# ComputeCalculator_V1_0.net
KiCad netlist of a schematic drawn in EAGLE
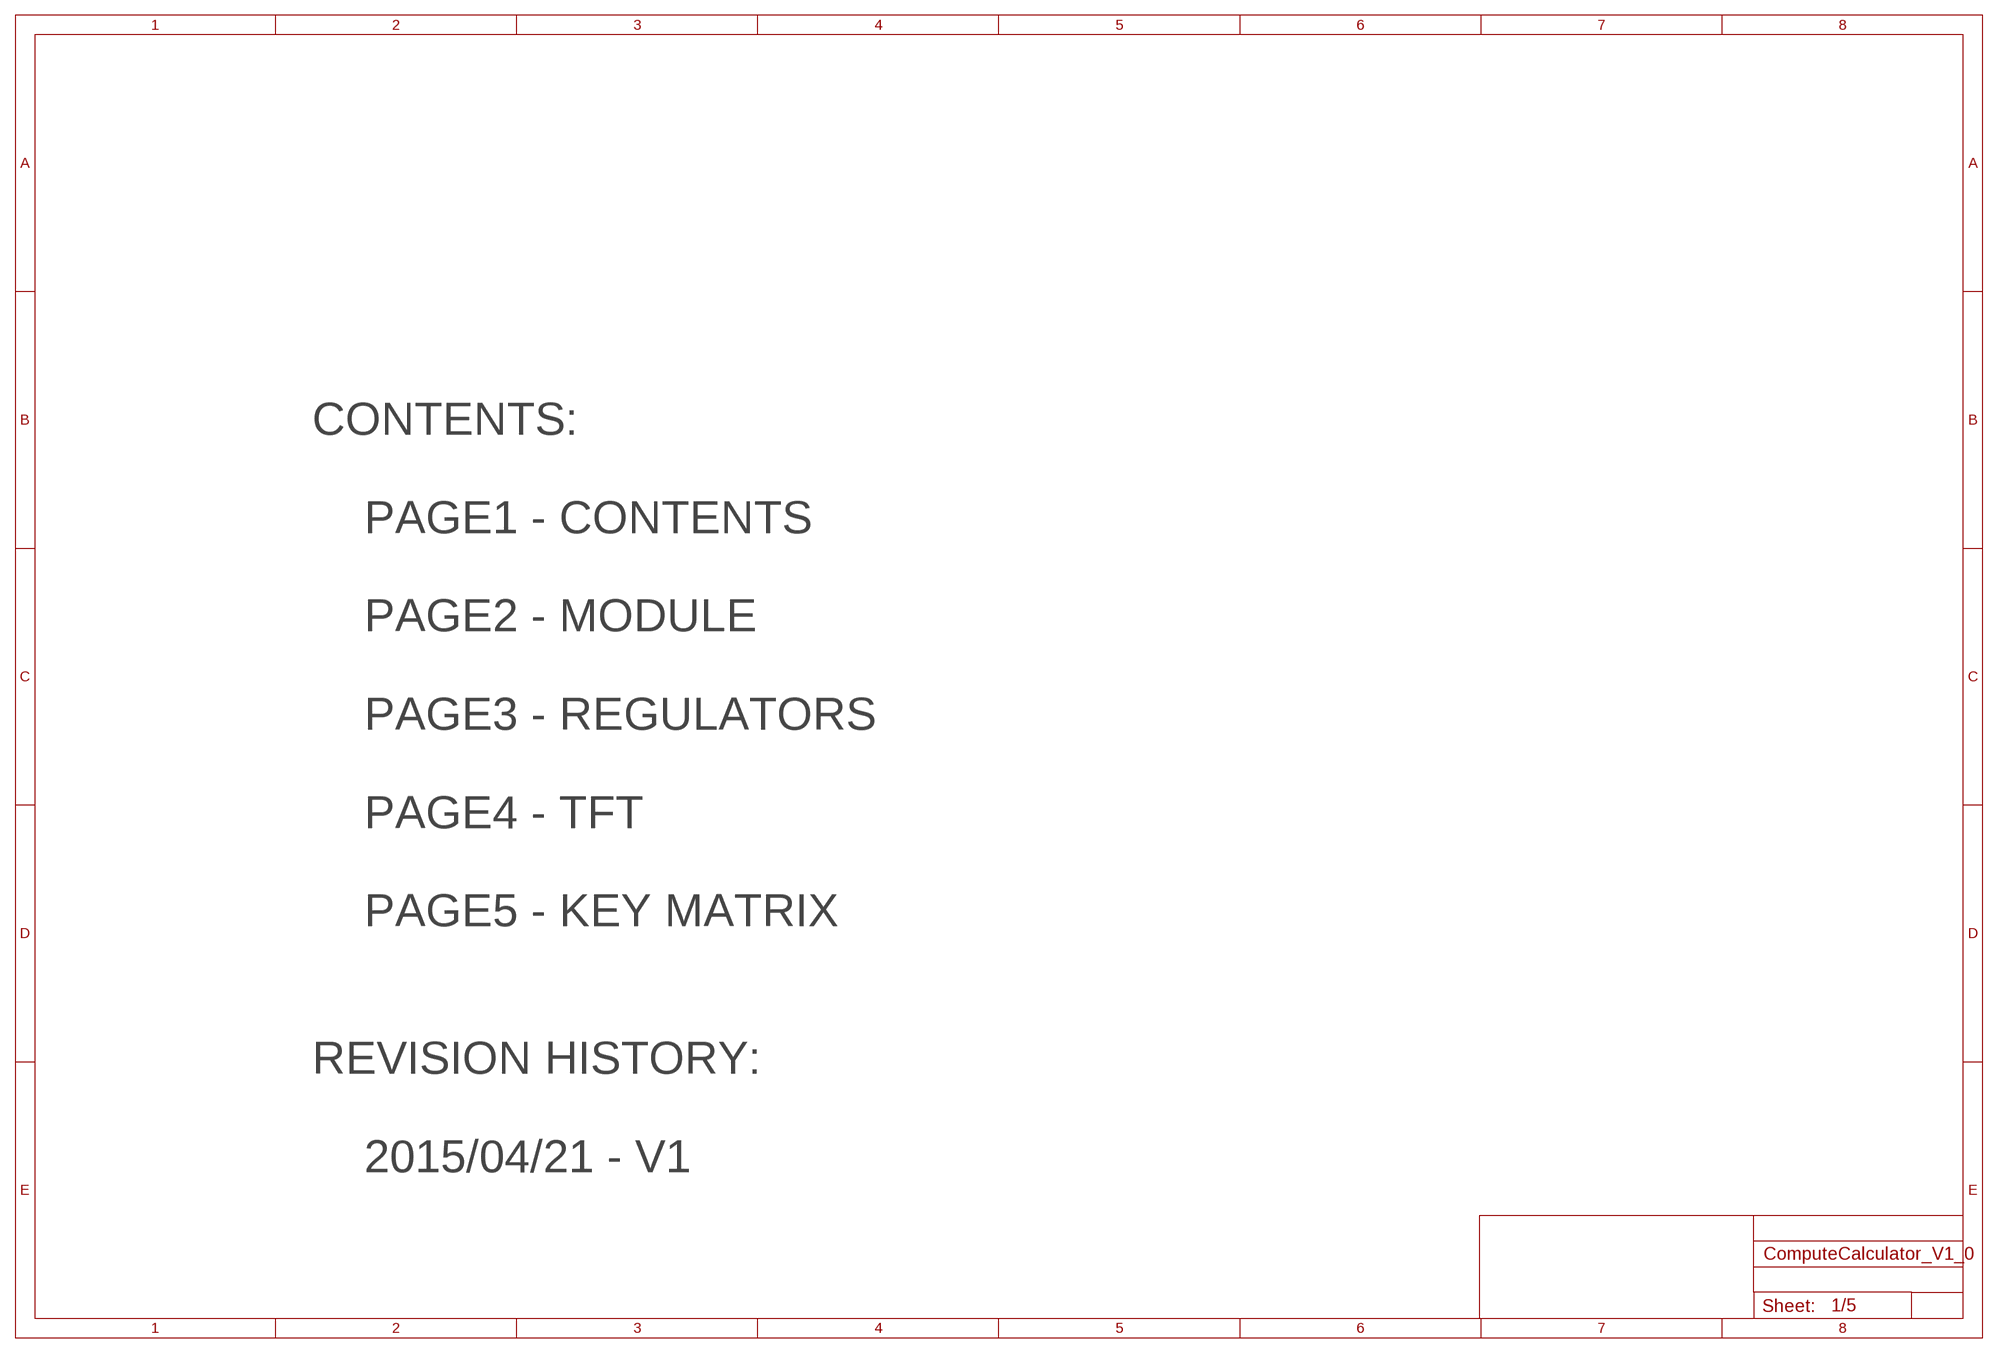
[diagram p0: schematic, sheet 1]
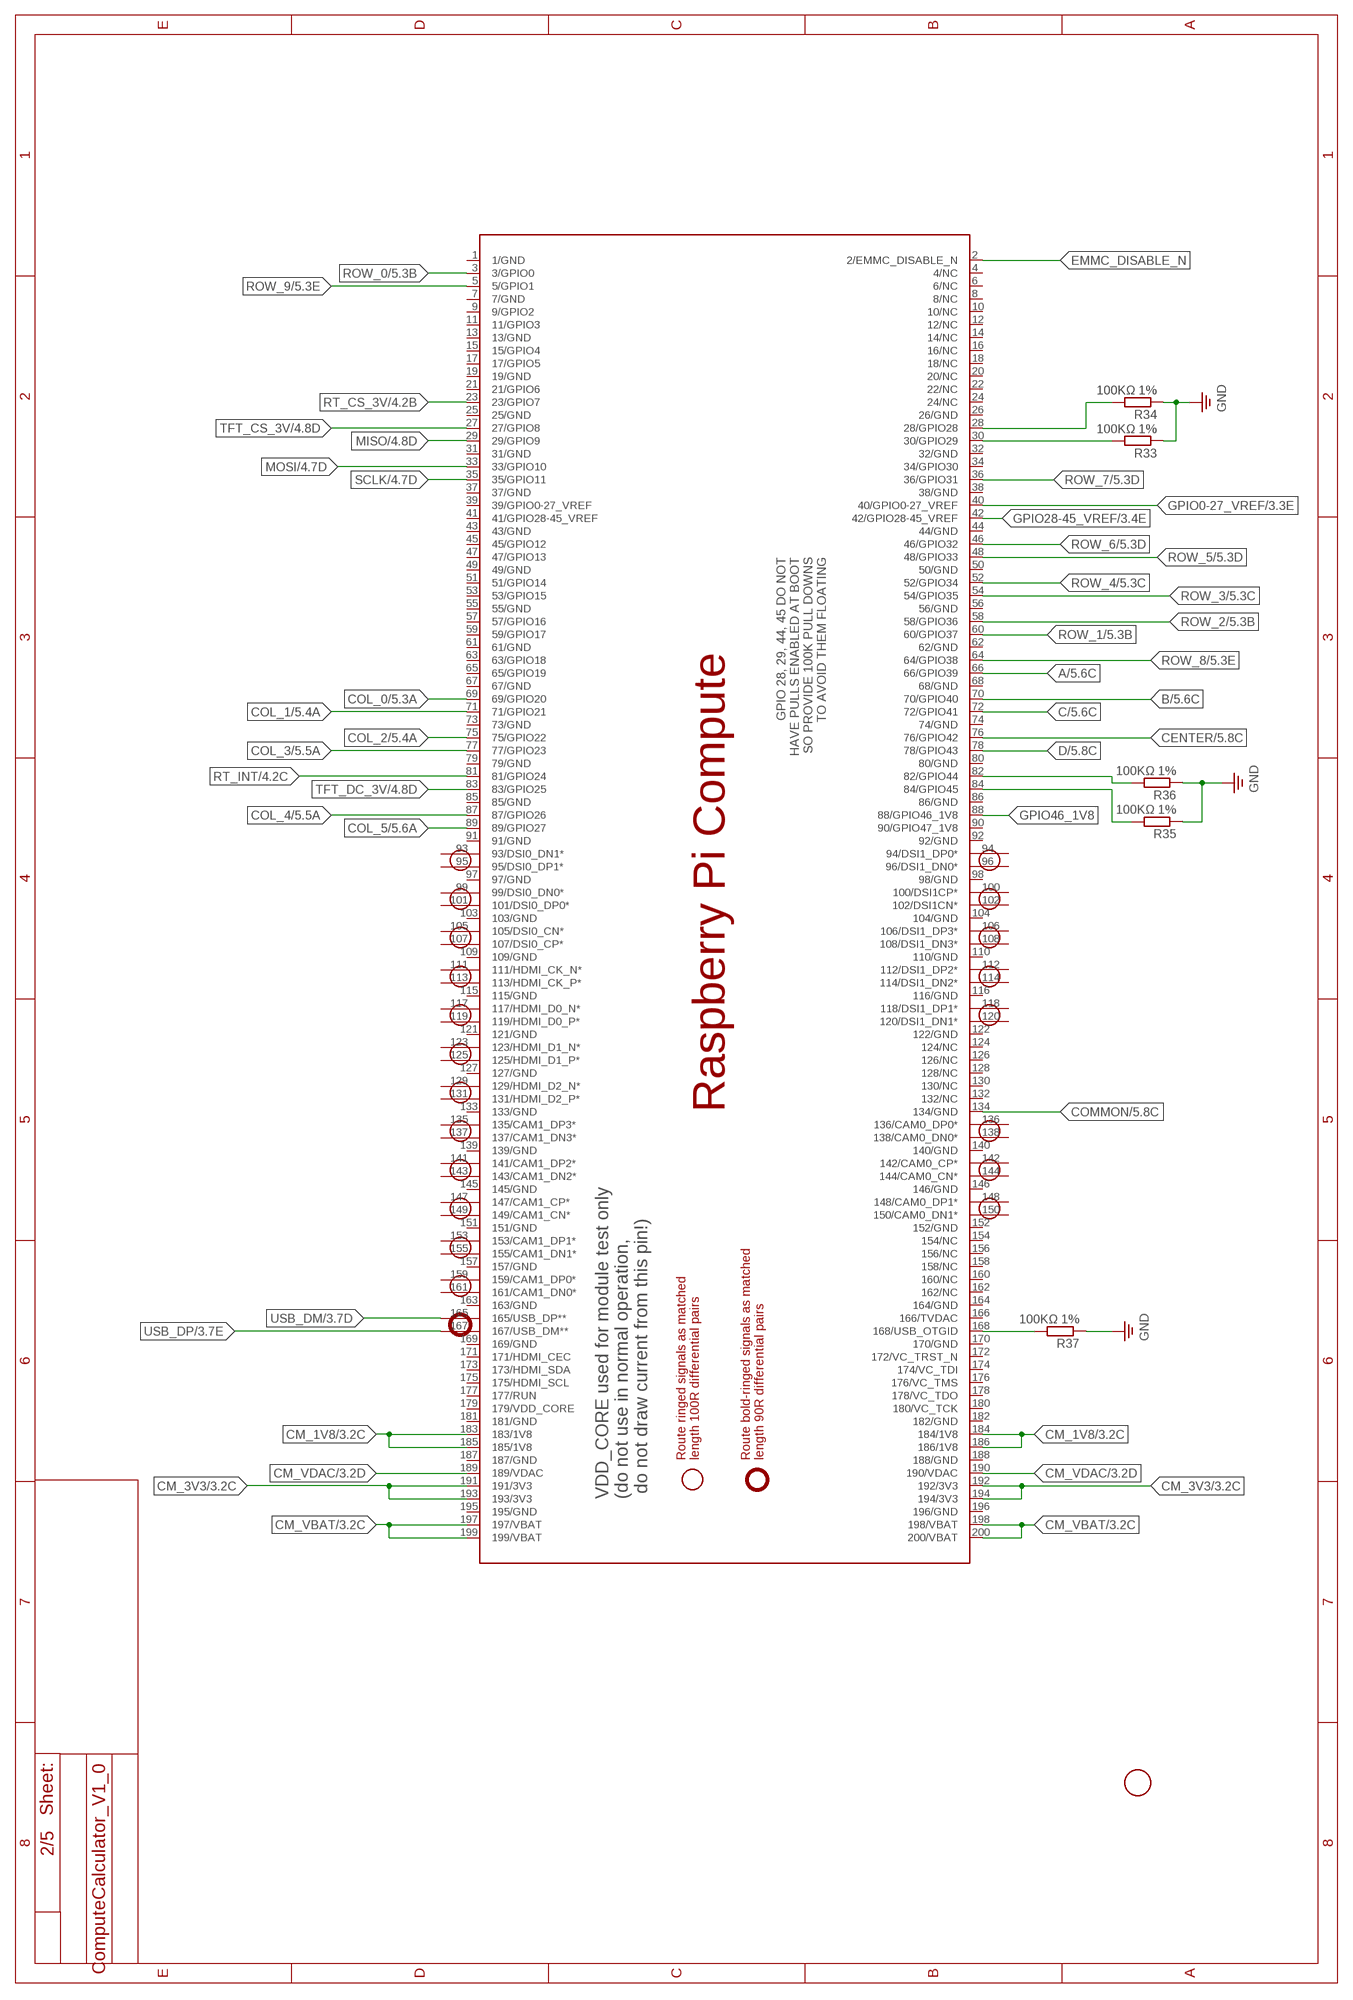
[diagram p1: schematic, sheet 2]
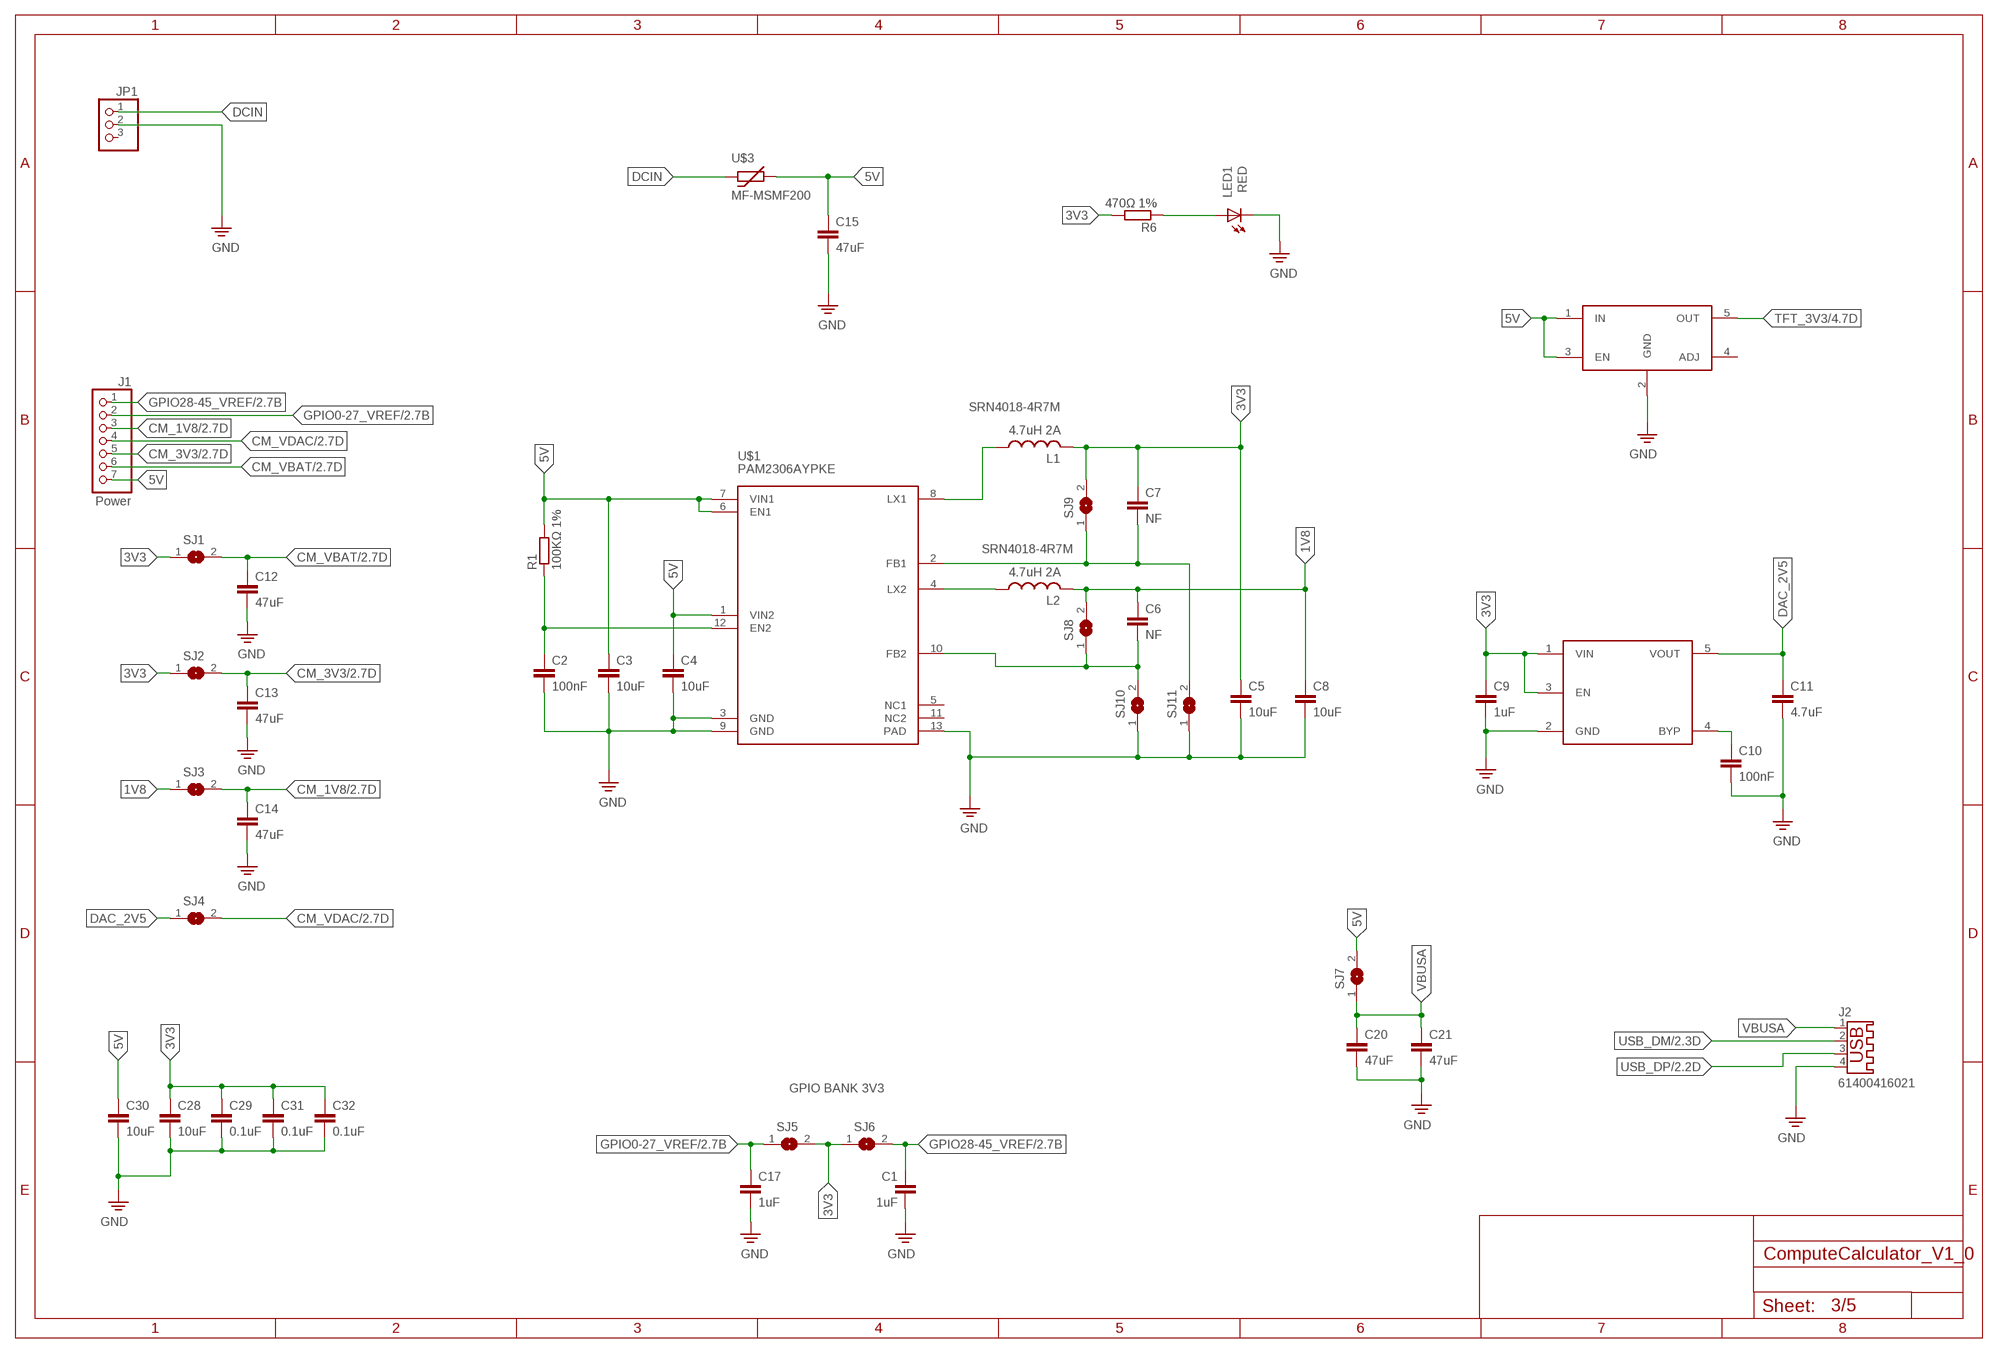
[diagram p2: schematic, sheet 3]
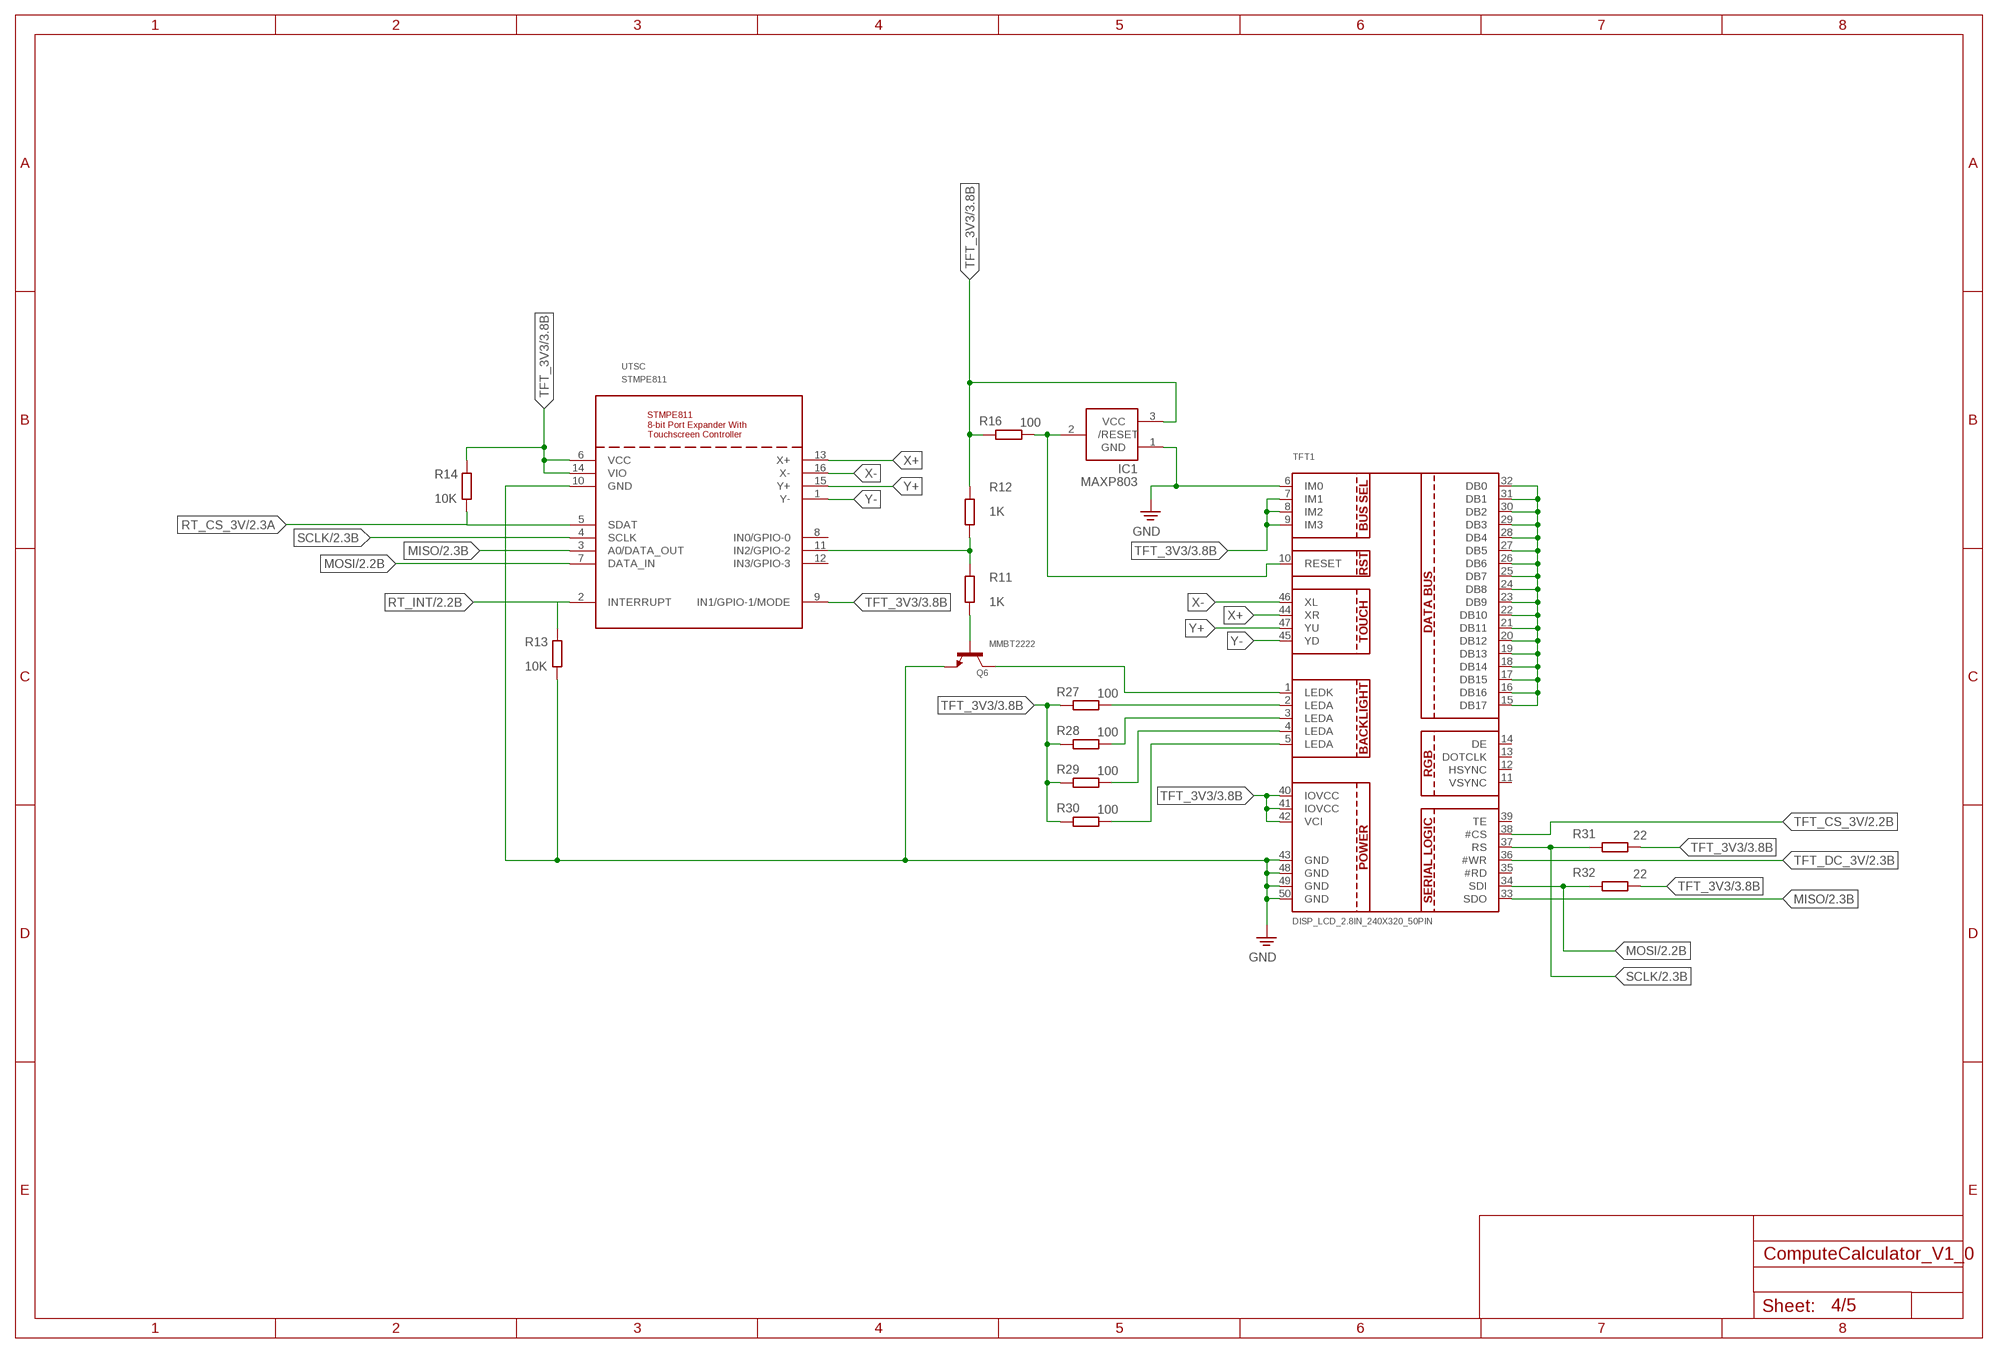
[diagram p3: schematic, sheet 4]
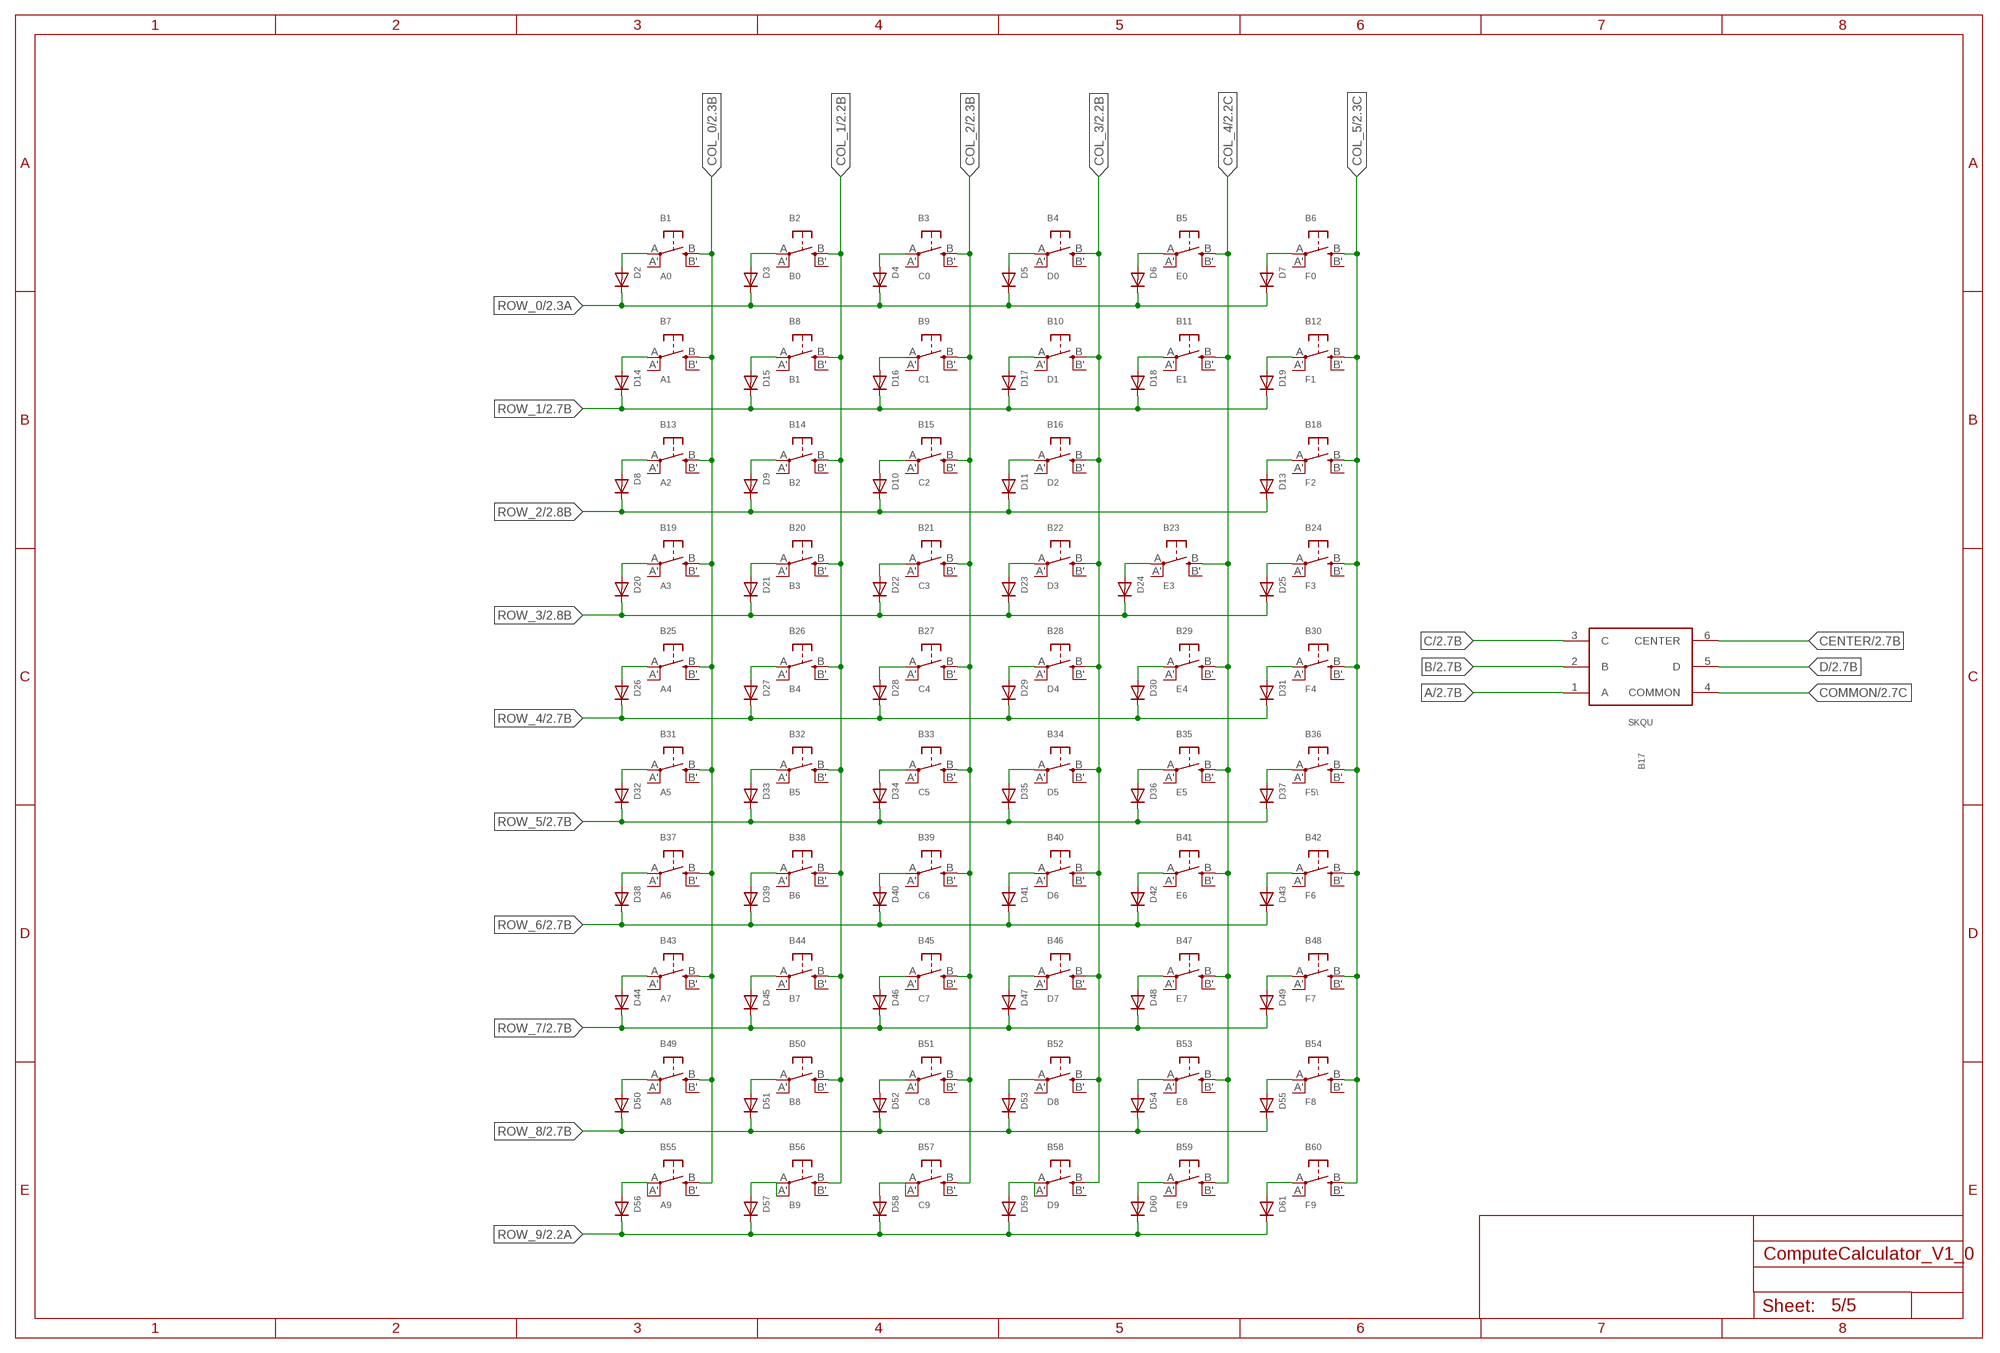
[diagram p4: schematic, sheet 5]

(export (version "E")
  (design (tool "Eeschema 10.0.6"))
  (components
    (comp (ref "B1")
      (value "A0")
      (footprint "eagle-import:EVQ-Q2")
      (libsource (lib "eagle-import") (part "SWITCH_TACT_SMT"))
    )
    (comp (ref "B2")
      (value "B0")
      (footprint "eagle-import:EVQ-Q2")
      (libsource (lib "eagle-import") (part "SWITCH_TACT_SMT"))
    )
    (comp (ref "B3")
      (value "C0")
      (footprint "eagle-import:EVQ-Q2")
      (libsource (lib "eagle-import") (part "SWITCH_TACT_SMT"))
    )
    (comp (ref "B4")
      (value "D0")
      (footprint "eagle-import:EVQ-Q2")
      (libsource (lib "eagle-import") (part "SWITCH_TACT_SMT"))
    )
    (comp (ref "B5")
      (value "E0")
      (footprint "eagle-import:EVQ-Q2")
      (libsource (lib "eagle-import") (part "SWITCH_TACT_SMT"))
    )
    (comp (ref "B6")
      (value "F0")
      (footprint "eagle-import:EVQ-Q2")
      (libsource (lib "eagle-import") (part "SWITCH_TACT_SMT"))
    )
    (comp (ref "B7")
      (value "A1")
      (footprint "eagle-import:EVQ-Q2")
      (libsource (lib "eagle-import") (part "SWITCH_TACT_SMT"))
    )
    (comp (ref "B8")
      (value "B1")
      (footprint "eagle-import:EVQ-Q2")
      (libsource (lib "eagle-import") (part "SWITCH_TACT_SMT"))
    )
    (comp (ref "B9")
      (value "C1")
      (footprint "eagle-import:EVQ-Q2")
      (libsource (lib "eagle-import") (part "SWITCH_TACT_SMT"))
    )
    (comp (ref "B10")
      (value "D1")
      (footprint "eagle-import:EVQ-Q2")
      (libsource (lib "eagle-import") (part "SWITCH_TACT_SMT"))
    )
    (comp (ref "B11")
      (value "E1")
      (footprint "eagle-import:EVQ-Q2")
      (libsource (lib "eagle-import") (part "SWITCH_TACT_SMT"))
    )
    (comp (ref "B12")
      (value "F1")
      (footprint "eagle-import:EVQ-Q2")
      (libsource (lib "eagle-import") (part "SWITCH_TACT_SMT"))
    )
    (comp (ref "B13")
      (value "A2")
      (footprint "eagle-import:EVQ-Q2")
      (libsource (lib "eagle-import") (part "SWITCH_TACT_SMT"))
    )
    (comp (ref "B14")
      (value "B2")
      (footprint "eagle-import:EVQ-Q2")
      (libsource (lib "eagle-import") (part "SWITCH_TACT_SMT"))
    )
    (comp (ref "B15")
      (value "C2")
      (footprint "eagle-import:EVQ-Q2")
      (libsource (lib "eagle-import") (part "SWITCH_TACT_SMT"))
    )
    (comp (ref "B16")
      (value "D2")
      (footprint "eagle-import:EVQ-Q2")
      (libsource (lib "eagle-import") (part "SWITCH_TACT_SMT"))
    )
    (comp (ref "B17")
      (value "SKQU")
      (footprint "eagle-import:SKQU")
      (libsource (lib "eagle-import") (part "SKQU"))
    )
    (comp (ref "B18")
      (value "F2")
      (footprint "eagle-import:EVQ-Q2")
      (libsource (lib "eagle-import") (part "SWITCH_TACT_SMT"))
    )
    (comp (ref "B19")
      (value "A3")
      (footprint "eagle-import:EVQ-Q2")
      (libsource (lib "eagle-import") (part "SWITCH_TACT_SMT"))
    )
    (comp (ref "B20")
      (value "B3")
      (footprint "eagle-import:EVQ-Q2")
      (libsource (lib "eagle-import") (part "SWITCH_TACT_SMT"))
    )
    (comp (ref "B21")
      (value "C3")
      (footprint "eagle-import:EVQ-Q2")
      (libsource (lib "eagle-import") (part "SWITCH_TACT_SMT"))
    )
    (comp (ref "B22")
      (value "D3")
      (footprint "eagle-import:EVQ-Q2")
      (libsource (lib "eagle-import") (part "SWITCH_TACT_SMT"))
    )
    (comp (ref "B23")
      (value "E3")
      (footprint "eagle-import:EVQ-Q2")
      (libsource (lib "eagle-import") (part "SWITCH_TACT_SMT"))
    )
    (comp (ref "B24")
      (value "F3")
      (footprint "eagle-import:EVQ-Q2")
      (libsource (lib "eagle-import") (part "SWITCH_TACT_SMT"))
    )
    (comp (ref "B25")
      (value "A4")
      (footprint "eagle-import:EVQ-Q2")
      (libsource (lib "eagle-import") (part "SWITCH_TACT_SMT"))
    )
    (comp (ref "B26")
      (value "B4")
      (footprint "eagle-import:EVQ-Q2")
      (libsource (lib "eagle-import") (part "SWITCH_TACT_SMT"))
    )
    (comp (ref "B27")
      (value "C4")
      (footprint "eagle-import:EVQ-Q2")
      (libsource (lib "eagle-import") (part "SWITCH_TACT_SMT"))
    )
    (comp (ref "B28")
      (value "D4")
      (footprint "eagle-import:EVQ-Q2")
      (libsource (lib "eagle-import") (part "SWITCH_TACT_SMT"))
    )
    (comp (ref "B29")
      (value "E4")
      (footprint "eagle-import:EVQ-Q2")
      (libsource (lib "eagle-import") (part "SWITCH_TACT_SMT"))
    )
    (comp (ref "B30")
      (value "F4")
      (footprint "eagle-import:EVQ-Q2")
      (libsource (lib "eagle-import") (part "SWITCH_TACT_SMT"))
    )
    (comp (ref "B31")
      (value "A5")
      (footprint "eagle-import:EVQ-Q2")
      (libsource (lib "eagle-import") (part "SWITCH_TACT_SMT"))
    )
    (comp (ref "B32")
      (value "B5")
      (footprint "eagle-import:EVQ-Q2")
      (libsource (lib "eagle-import") (part "SWITCH_TACT_SMT"))
    )
    (comp (ref "B33")
      (value "C5")
      (footprint "eagle-import:EVQ-Q2")
      (libsource (lib "eagle-import") (part "SWITCH_TACT_SMT"))
    )
    (comp (ref "B34")
      (value "D5")
      (footprint "eagle-import:EVQ-Q2")
      (libsource (lib "eagle-import") (part "SWITCH_TACT_SMT"))
    )
    (comp (ref "B35")
      (value "E5")
      (footprint "eagle-import:EVQ-Q2")
      (libsource (lib "eagle-import") (part "SWITCH_TACT_SMT"))
    )
    (comp (ref "B36")
      (value "F5\\")
      (footprint "eagle-import:EVQ-Q2")
      (libsource (lib "eagle-import") (part "SWITCH_TACT_SMT"))
    )
    (comp (ref "B37")
      (value "A6")
      (footprint "eagle-import:EVQ-Q2")
      (libsource (lib "eagle-import") (part "SWITCH_TACT_SMT"))
    )
    (comp (ref "B38")
      (value "B6")
      (footprint "eagle-import:EVQ-Q2")
      (libsource (lib "eagle-import") (part "SWITCH_TACT_SMT"))
    )
    (comp (ref "B39")
      (value "C6")
      (footprint "eagle-import:EVQ-Q2")
      (libsource (lib "eagle-import") (part "SWITCH_TACT_SMT"))
    )
    (comp (ref "B40")
      (value "D6")
      (footprint "eagle-import:EVQ-Q2")
      (libsource (lib "eagle-import") (part "SWITCH_TACT_SMT"))
    )
    (comp (ref "B41")
      (value "E6")
      (footprint "eagle-import:EVQ-Q2")
      (libsource (lib "eagle-import") (part "SWITCH_TACT_SMT"))
    )
    (comp (ref "B42")
      (value "F6")
      (footprint "eagle-import:EVQ-Q2")
      (libsource (lib "eagle-import") (part "SWITCH_TACT_SMT"))
    )
    (comp (ref "B43")
      (value "A7")
      (footprint "eagle-import:EVQ-Q2")
      (libsource (lib "eagle-import") (part "SWITCH_TACT_SMT"))
    )
    (comp (ref "B44")
      (value "B7")
      (footprint "eagle-import:EVQ-Q2")
      (libsource (lib "eagle-import") (part "SWITCH_TACT_SMT"))
    )
    (comp (ref "B45")
      (value "C7")
      (footprint "eagle-import:EVQ-Q2")
      (libsource (lib "eagle-import") (part "SWITCH_TACT_SMT"))
    )
    (comp (ref "B46")
      (value "D7")
      (footprint "eagle-import:EVQ-Q2")
      (libsource (lib "eagle-import") (part "SWITCH_TACT_SMT"))
    )
    (comp (ref "B47")
      (value "E7")
      (footprint "eagle-import:EVQ-Q2")
      (libsource (lib "eagle-import") (part "SWITCH_TACT_SMT"))
    )
    (comp (ref "B48")
      (value "F7")
      (footprint "eagle-import:EVQ-Q2")
      (libsource (lib "eagle-import") (part "SWITCH_TACT_SMT"))
    )
    (comp (ref "B49")
      (value "A8")
      (footprint "eagle-import:EVQ-Q2")
      (libsource (lib "eagle-import") (part "SWITCH_TACT_SMT"))
    )
    (comp (ref "B50")
      (value "B8")
      (footprint "eagle-import:EVQ-Q2")
      (libsource (lib "eagle-import") (part "SWITCH_TACT_SMT"))
    )
    (comp (ref "B51")
      (value "C8")
      (footprint "eagle-import:EVQ-Q2")
      (libsource (lib "eagle-import") (part "SWITCH_TACT_SMT"))
    )
    (comp (ref "B52")
      (value "D8")
      (footprint "eagle-import:EVQ-Q2")
      (libsource (lib "eagle-import") (part "SWITCH_TACT_SMT"))
    )
    (comp (ref "B53")
      (value "E8")
      (footprint "eagle-import:EVQ-Q2")
      (libsource (lib "eagle-import") (part "SWITCH_TACT_SMT"))
    )
    (comp (ref "B54")
      (value "F8")
      (footprint "eagle-import:EVQ-Q2")
      (libsource (lib "eagle-import") (part "SWITCH_TACT_SMT"))
    )
    (comp (ref "B55")
      (value "A9")
      (footprint "eagle-import:EVQ-Q2")
      (libsource (lib "eagle-import") (part "SWITCH_TACT_SMT"))
    )
    (comp (ref "B56")
      (value "B9")
      (footprint "eagle-import:EVQ-Q2")
      (libsource (lib "eagle-import") (part "SWITCH_TACT_SMT"))
    )
    (comp (ref "B57")
      (value "C9")
      (footprint "eagle-import:EVQ-Q2")
      (libsource (lib "eagle-import") (part "SWITCH_TACT_SMT"))
    )
    (comp (ref "B58")
      (value "D9")
      (footprint "eagle-import:EVQ-Q2")
      (libsource (lib "eagle-import") (part "SWITCH_TACT_SMT"))
    )
    (comp (ref "B59")
      (value "E9")
      (footprint "eagle-import:EVQ-Q2")
      (libsource (lib "eagle-import") (part "SWITCH_TACT_SMT"))
    )
    (comp (ref "B60")
      (value "F9")
      (footprint "eagle-import:EVQ-Q2")
      (libsource (lib "eagle-import") (part "SWITCH_TACT_SMT"))
    )
    (comp (ref "D2")
      (value "DIODESMA")
      (footprint "eagle-import:SMADIODE")
      (libsource (lib "eagle-import") (part "DIODESMA"))
    )
    (comp (ref "D3")
      (value "DIODESMA")
      (footprint "eagle-import:SMADIODE")
      (libsource (lib "eagle-import") (part "DIODESMA"))
    )
    (comp (ref "D4")
      (value "DIODESMA")
      (footprint "eagle-import:SMADIODE")
      (libsource (lib "eagle-import") (part "DIODESMA"))
    )
    (comp (ref "D5")
      (value "DIODESMA")
      (footprint "eagle-import:SMADIODE")
      (libsource (lib "eagle-import") (part "DIODESMA"))
    )
    (comp (ref "D6")
      (value "DIODESMA")
      (footprint "eagle-import:SMADIODE")
      (libsource (lib "eagle-import") (part "DIODESMA"))
    )
    (comp (ref "D7")
      (value "DIODESMA")
      (footprint "eagle-import:SMADIODE")
      (libsource (lib "eagle-import") (part "DIODESMA"))
    )
    (comp (ref "D8")
      (value "DIODESMA")
      (footprint "eagle-import:SMADIODE")
      (libsource (lib "eagle-import") (part "DIODESMA"))
    )
    (comp (ref "D9")
      (value "DIODESMA")
      (footprint "eagle-import:SMADIODE")
      (libsource (lib "eagle-import") (part "DIODESMA"))
    )
    (comp (ref "D10")
      (value "DIODESMA")
      (footprint "eagle-import:SMADIODE")
      (libsource (lib "eagle-import") (part "DIODESMA"))
    )
    (comp (ref "D11")
      (value "DIODESMA")
      (footprint "eagle-import:SMADIODE")
      (libsource (lib "eagle-import") (part "DIODESMA"))
    )
    (comp (ref "D13")
      (value "DIODESMA")
      (footprint "eagle-import:SMADIODE")
      (libsource (lib "eagle-import") (part "DIODESMA"))
    )
    (comp (ref "D14")
      (value "DIODESMA")
      (footprint "eagle-import:SMADIODE")
      (libsource (lib "eagle-import") (part "DIODESMA"))
    )
    (comp (ref "D15")
      (value "DIODESMA")
      (footprint "eagle-import:SMADIODE")
      (libsource (lib "eagle-import") (part "DIODESMA"))
    )
    (comp (ref "D16")
      (value "DIODESMA")
      (footprint "eagle-import:SMADIODE")
      (libsource (lib "eagle-import") (part "DIODESMA"))
    )
    (comp (ref "D17")
      (value "DIODESMA")
      (footprint "eagle-import:SMADIODE")
      (libsource (lib "eagle-import") (part "DIODESMA"))
    )
    (comp (ref "D18")
      (value "DIODESMA")
      (footprint "eagle-import:SMADIODE")
      (libsource (lib "eagle-import") (part "DIODESMA"))
    )
    (comp (ref "D19")
      (value "DIODESMA")
      (footprint "eagle-import:SMADIODE")
      (libsource (lib "eagle-import") (part "DIODESMA"))
    )
    (comp (ref "D20")
      (value "DIODESMA")
      (footprint "eagle-import:SMADIODE")
      (libsource (lib "eagle-import") (part "DIODESMA"))
    )
    (comp (ref "D21")
      (value "DIODESMA")
      (footprint "eagle-import:SMADIODE")
      (libsource (lib "eagle-import") (part "DIODESMA"))
    )
    (comp (ref "D22")
      (value "DIODESMA")
      (footprint "eagle-import:SMADIODE")
      (libsource (lib "eagle-import") (part "DIODESMA"))
    )
    (comp (ref "D23")
      (value "DIODESMA")
      (footprint "eagle-import:SMADIODE")
      (libsource (lib "eagle-import") (part "DIODESMA"))
    )
    (comp (ref "D24")
      (value "DIODESMA")
      (footprint "eagle-import:SMADIODE")
      (libsource (lib "eagle-import") (part "DIODESMA"))
    )
    (comp (ref "D25")
      (value "DIODESMA")
      (footprint "eagle-import:SMADIODE")
      (libsource (lib "eagle-import") (part "DIODESMA"))
    )
    (comp (ref "D26")
      (value "DIODESMA")
      (footprint "eagle-import:SMADIODE")
      (libsource (lib "eagle-import") (part "DIODESMA"))
    )
    (comp (ref "D27")
      (value "DIODESMA")
      (footprint "eagle-import:SMADIODE")
      (libsource (lib "eagle-import") (part "DIODESMA"))
    )
    (comp (ref "D28")
      (value "DIODESMA")
      (footprint "eagle-import:SMADIODE")
      (libsource (lib "eagle-import") (part "DIODESMA"))
    )
    (comp (ref "D29")
      (value "DIODESMA")
      (footprint "eagle-import:SMADIODE")
      (libsource (lib "eagle-import") (part "DIODESMA"))
    )
    (comp (ref "D30")
      (value "DIODESMA")
      (footprint "eagle-import:SMADIODE")
      (libsource (lib "eagle-import") (part "DIODESMA"))
    )
    (comp (ref "D31")
      (value "DIODESMA")
      (footprint "eagle-import:SMADIODE")
      (libsource (lib "eagle-import") (part "DIODESMA"))
    )
    (comp (ref "D32")
      (value "DIODESMA")
      (footprint "eagle-import:SMADIODE")
      (libsource (lib "eagle-import") (part "DIODESMA"))
    )
    (comp (ref "D33")
      (value "DIODESMA")
      (footprint "eagle-import:SMADIODE")
      (libsource (lib "eagle-import") (part "DIODESMA"))
    )
    (comp (ref "D34")
      (value "DIODESMA")
      (footprint "eagle-import:SMADIODE")
      (libsource (lib "eagle-import") (part "DIODESMA"))
    )
    (comp (ref "D35")
      (value "DIODESMA")
      (footprint "eagle-import:SMADIODE")
      (libsource (lib "eagle-import") (part "DIODESMA"))
    )
    (comp (ref "D36")
      (value "DIODESMA")
      (footprint "eagle-import:SMADIODE")
      (libsource (lib "eagle-import") (part "DIODESMA"))
    )
    (comp (ref "D37")
      (value "DIODESMA")
      (footprint "eagle-import:SMADIODE")
      (libsource (lib "eagle-import") (part "DIODESMA"))
    )
    (comp (ref "D38")
      (value "DIODESMA")
      (footprint "eagle-import:SMADIODE")
      (libsource (lib "eagle-import") (part "DIODESMA"))
    )
    (comp (ref "D39")
      (value "DIODESMA")
      (footprint "eagle-import:SMADIODE")
      (libsource (lib "eagle-import") (part "DIODESMA"))
    )
    (comp (ref "D40")
      (value "DIODESMA")
      (footprint "eagle-import:SMADIODE")
      (libsource (lib "eagle-import") (part "DIODESMA"))
    )
    (comp (ref "D41")
      (value "DIODESMA")
      (footprint "eagle-import:SMADIODE")
      (libsource (lib "eagle-import") (part "DIODESMA"))
    )
    (comp (ref "D42")
      (value "DIODESMA")
      (footprint "eagle-import:SMADIODE")
      (libsource (lib "eagle-import") (part "DIODESMA"))
    )
    (comp (ref "D43")
      (value "DIODESMA")
      (footprint "eagle-import:SMADIODE")
      (libsource (lib "eagle-import") (part "DIODESMA"))
    )
    (comp (ref "D44")
      (value "DIODESMA")
      (footprint "eagle-import:SMADIODE")
      (libsource (lib "eagle-import") (part "DIODESMA"))
    )
    (comp (ref "D45")
      (value "DIODESMA")
      (footprint "eagle-import:SMADIODE")
      (libsource (lib "eagle-import") (part "DIODESMA"))
    )
    (comp (ref "D46")
      (value "DIODESMA")
      (footprint "eagle-import:SMADIODE")
      (libsource (lib "eagle-import") (part "DIODESMA"))
    )
    (comp (ref "D47")
      (value "DIODESMA")
      (footprint "eagle-import:SMADIODE")
      (libsource (lib "eagle-import") (part "DIODESMA"))
    )
    (comp (ref "D48")
      (value "DIODESMA")
      (footprint "eagle-import:SMADIODE")
      (libsource (lib "eagle-import") (part "DIODESMA"))
    )
    (comp (ref "D49")
      (value "DIODESMA")
      (footprint "eagle-import:SMADIODE")
      (libsource (lib "eagle-import") (part "DIODESMA"))
    )
    (comp (ref "D50")
      (value "DIODESMA")
      (footprint "eagle-import:SMADIODE")
      (libsource (lib "eagle-import") (part "DIODESMA"))
    )
    (comp (ref "D51")
      (value "DIODESMA")
      (footprint "eagle-import:SMADIODE")
      (libsource (lib "eagle-import") (part "DIODESMA"))
    )
    (comp (ref "D52")
      (value "DIODESMA")
      (footprint "eagle-import:SMADIODE")
      (libsource (lib "eagle-import") (part "DIODESMA"))
    )
    (comp (ref "D53")
      (value "DIODESMA")
      (footprint "eagle-import:SMADIODE")
      (libsource (lib "eagle-import") (part "DIODESMA"))
    )
    (comp (ref "D54")
      (value "DIODESMA")
      (footprint "eagle-import:SMADIODE")
      (libsource (lib "eagle-import") (part "DIODESMA"))
    )
    (comp (ref "D55")
      (value "DIODESMA")
      (footprint "eagle-import:SMADIODE")
      (libsource (lib "eagle-import") (part "DIODESMA"))
    )
    (comp (ref "D56")
      (value "DIODESMA")
      (footprint "eagle-import:SMADIODE")
      (libsource (lib "eagle-import") (part "DIODESMA"))
    )
    (comp (ref "D57")
      (value "DIODESMA")
      (footprint "eagle-import:SMADIODE")
      (libsource (lib "eagle-import") (part "DIODESMA"))
    )
    (comp (ref "D58")
      (value "DIODESMA")
      (footprint "eagle-import:SMADIODE")
      (libsource (lib "eagle-import") (part "DIODESMA"))
    )
    (comp (ref "D59")
      (value "DIODESMA")
      (footprint "eagle-import:SMADIODE")
      (libsource (lib "eagle-import") (part "DIODESMA"))
    )
    (comp (ref "D60")
      (value "DIODESMA")
      (footprint "eagle-import:SMADIODE")
      (libsource (lib "eagle-import") (part "DIODESMA"))
    )
    (comp (ref "D61")
      (value "DIODESMA")
      (footprint "eagle-import:SMADIODE")
      (libsource (lib "eagle-import") (part "DIODESMA"))
    )
    (comp (ref "IC1")
      (value "MAXP803")
      (footprint "eagle-import:SOT23")
      (libsource (lib "eagle-import") (part "AXP083-SAG"))
    )
    (comp (ref "Q6")
      (value "MMBT2222")
      (footprint "eagle-import:SOT23-WIDE")
      (libsource (lib "eagle-import") (part "TRANSISTOR_NPNWIDE"))
    )
    (comp (ref "R11")
      (value "1K")
      (footprint "eagle-import:M1206")
      (libsource (lib "eagle-import") (part "R-EU_M1206"))
    )
    (comp (ref "R12")
      (value "1K")
      (footprint "eagle-import:M1206")
      (libsource (lib "eagle-import") (part "R-EU_M1206"))
    )
    (comp (ref "R13")
      (value "10K")
      (footprint "eagle-import:M1206")
      (libsource (lib "eagle-import") (part "R-EU_M1206"))
    )
    (comp (ref "R14")
      (value "10K")
      (footprint "eagle-import:M1206")
      (libsource (lib "eagle-import") (part "R-EU_M1206"))
    )
    (comp (ref "R16")
      (value "100")
      (footprint "eagle-import:M1206")
      (libsource (lib "eagle-import") (part "R-EU_M1206"))
    )
    (comp (ref "R27")
      (value "100")
      (footprint "eagle-import:M1206")
      (libsource (lib "eagle-import") (part "R-EU_M1206"))
    )
    (comp (ref "R28")
      (value "100")
      (footprint "eagle-import:M1206")
      (libsource (lib "eagle-import") (part "R-EU_M1206"))
    )
    (comp (ref "R29")
      (value "100")
      (footprint "eagle-import:M1206")
      (libsource (lib "eagle-import") (part "R-EU_M1206"))
    )
    (comp (ref "R30")
      (value "100")
      (footprint "eagle-import:M1206")
      (libsource (lib "eagle-import") (part "R-EU_M1206"))
    )
    (comp (ref "R31")
      (value "22")
      (footprint "eagle-import:M1206")
      (libsource (lib "eagle-import") (part "R-EU_M1206"))
    )
    (comp (ref "R32")
      (value "22")
      (footprint "eagle-import:M1206")
      (libsource (lib "eagle-import") (part "R-EU_M1206"))
    )
    (comp (ref "TFT1")
      (value "DISP_LCD_2.8IN_240X320_50PIN")
      (footprint "eagle-import:TFT_2.83IN_240X320_50PIN")
      (libsource (lib "eagle-import") (part "DISP_LCD_2.8IN_240X320_50PIN"))
    )
    (comp (ref "UTSC")
      (value "STMPE811")
      (footprint "eagle-import:QFN16L")
      (libsource (lib "eagle-import") (part "STMPE811"))
    )
    (comp (ref "PCB1")
      (value "RPI_COMPUTE")
      (footprint "eagle-import:RPI_COMPUTE")
      (libsource (lib "eagle-import") (part "RPI_COMPUTE"))
    )
    (comp (ref "R33")
      (value "100KΩ 1%")
      (footprint "eagle-import:M1206")
      (libsource (lib "eagle-import") (part "R-EU_M1206"))
    )
    (comp (ref "R34")
      (value "100KΩ 1%")
      (footprint "eagle-import:M1206")
      (libsource (lib "eagle-import") (part "R-EU_M1206"))
    )
    (comp (ref "R35")
      (value "100KΩ 1%")
      (footprint "eagle-import:M1206")
      (libsource (lib "eagle-import") (part "R-EU_M1206"))
    )
    (comp (ref "R36")
      (value "100KΩ 1%")
      (footprint "eagle-import:M1206")
      (libsource (lib "eagle-import") (part "R-EU_M1206"))
    )
    (comp (ref "R37")
      (value "100KΩ 1%")
      (footprint "eagle-import:M1206")
      (libsource (lib "eagle-import") (part "R-EU_M1206"))
    )
    (comp (ref "U$2")
      (value "FIDUCIAL")
      (footprint "eagle-import:FIDUCIAL_1MM")
      (libsource (lib "eagle-import") (part "FIDUCIAL"))
    )
    (comp (ref "C1")
      (value "1uF")
      (footprint "eagle-import:C1206")
      (libsource (lib "eagle-import") (part "C-EUC1206"))
    )
    (comp (ref "C2")
      (value "100nF")
      (footprint "eagle-import:C1206")
      (libsource (lib "eagle-import") (part "C-EUC1206"))
    )
    (comp (ref "C3")
      (value "10uF")
      (footprint "eagle-import:C1206")
      (libsource (lib "eagle-import") (part "C-EUC1206"))
    )
    (comp (ref "C4")
      (value "10uF")
      (footprint "eagle-import:C1206")
      (libsource (lib "eagle-import") (part "C-EUC1206"))
    )
    (comp (ref "C5")
      (value "10uF")
      (footprint "eagle-import:C1206")
      (libsource (lib "eagle-import") (part "C-EUC1206"))
    )
    (comp (ref "C6")
      (value "NF")
      (footprint "eagle-import:C1206")
      (libsource (lib "eagle-import") (part "C-EUC1206"))
    )
    (comp (ref "C7")
      (value "NF")
      (footprint "eagle-import:C1206")
      (libsource (lib "eagle-import") (part "C-EUC1206"))
    )
    (comp (ref "C8")
      (value "10uF")
      (footprint "eagle-import:C1206")
      (libsource (lib "eagle-import") (part "C-EUC1206"))
    )
    (comp (ref "C9")
      (value "1uF")
      (footprint "eagle-import:C1206")
      (libsource (lib "eagle-import") (part "C-EUC1206"))
    )
    (comp (ref "C10")
      (value "100nF")
      (footprint "eagle-import:C1206")
      (libsource (lib "eagle-import") (part "C-EUC1206"))
    )
    (comp (ref "C11")
      (value "4.7uF")
      (footprint "eagle-import:C1206")
      (libsource (lib "eagle-import") (part "C-EUC1206"))
    )
    (comp (ref "C12")
      (value "47uF")
      (footprint "eagle-import:C1206")
      (libsource (lib "eagle-import") (part "C-EUC1206"))
    )
    (comp (ref "C13")
      (value "47uF")
      (footprint "eagle-import:C1206")
      (libsource (lib "eagle-import") (part "C-EUC1206"))
    )
    (comp (ref "C14")
      (value "47uF")
      (footprint "eagle-import:C1206")
      (libsource (lib "eagle-import") (part "C-EUC1206"))
    )
    (comp (ref "C15")
      (value "47uF")
      (footprint "eagle-import:C0603")
      (libsource (lib "eagle-import") (part "CAPACITOR"))
    )
    (comp (ref "C17")
      (value "1uF")
      (footprint "eagle-import:C1206")
      (libsource (lib "eagle-import") (part "C-EUC1206"))
    )
    (comp (ref "C20")
      (value "47uF")
      (footprint "eagle-import:C1206")
      (libsource (lib "eagle-import") (part "C-EUC1206"))
    )
    (comp (ref "C21")
      (value "47uF")
      (footprint "eagle-import:C1206")
      (libsource (lib "eagle-import") (part "C-EUC1206"))
    )
    (comp (ref "C28")
      (value "10uF")
      (footprint "eagle-import:C1206")
      (libsource (lib "eagle-import") (part "C-EUC1206"))
    )
    (comp (ref "C29")
      (value "0.1uF")
      (footprint "eagle-import:C1206")
      (libsource (lib "eagle-import") (part "C-EUC1206"))
    )
    (comp (ref "C30")
      (value "10uF")
      (footprint "eagle-import:C1206")
      (libsource (lib "eagle-import") (part "C-EUC1206"))
    )
    (comp (ref "C31")
      (value "0.1uF")
      (footprint "eagle-import:C1206")
      (libsource (lib "eagle-import") (part "C-EUC1206"))
    )
    (comp (ref "C32")
      (value "0.1uF")
      (footprint "eagle-import:C1206")
      (libsource (lib "eagle-import") (part "C-EUC1206"))
    )
    (comp (ref "J1")
      (value "Power")
      (footprint "eagle-import:1X7-BIG")
      (libsource (lib "eagle-import") (part "1X7-BIG"))
    )
    (comp (ref "J2")
      (value "61400416021")
      (footprint "eagle-import:USB-A003")
      (libsource (lib "eagle-import") (part "USB-A003"))
    )
    (comp (ref "JP1")
      (value "PINHD-1X3")
      (footprint "eagle-import:1X03")
      (libsource (lib "eagle-import") (part "PINHD-1X3"))
    )
    (comp (ref "L1")
      (value "SRN4018-4R7M")
      (footprint "eagle-import:POWER-CHOKE_WE-TPC")
      (libsource (lib "eagle-import") (part "L-USWE-TPC"))
    )
    (comp (ref "L2")
      (value "SRN4018-4R7M")
      (footprint "eagle-import:POWER-CHOKE_WE-TPC")
      (libsource (lib "eagle-import") (part "L-USWE-TPC"))
    )
    (comp (ref "LED1")
      (value "RED")
      (footprint "eagle-import:CHIP-LED0805")
      (libsource (lib "eagle-import") (part "LEDCHIP-LED0805"))
    )
    (comp (ref "R1")
      (value "100KΩ 1%")
      (footprint "eagle-import:M1206")
      (libsource (lib "eagle-import") (part "R-EU_M1206"))
    )
    (comp (ref "R6")
      (value "470Ω 1%")
      (footprint "eagle-import:M1206")
      (libsource (lib "eagle-import") (part "R-EU_M1206"))
    )
    (comp (ref "SJ1")
      (value "JUMPER")
      (footprint "eagle-import:SJW")
      (libsource (lib "eagle-import") (part "JUMPER"))
    )
    (comp (ref "SJ2")
      (value "JUMPER")
      (footprint "eagle-import:SJW")
      (libsource (lib "eagle-import") (part "JUMPER"))
    )
    (comp (ref "SJ3")
      (value "JUMPER")
      (footprint "eagle-import:SJW")
      (libsource (lib "eagle-import") (part "JUMPER"))
    )
    (comp (ref "SJ4")
      (value "JUMPER")
      (footprint "eagle-import:SJW")
      (libsource (lib "eagle-import") (part "JUMPER"))
    )
    (comp (ref "SJ5")
      (value "JUMPER")
      (footprint "eagle-import:SJW")
      (libsource (lib "eagle-import") (part "JUMPER"))
    )
    (comp (ref "SJ6")
      (value "JUMPER")
      (footprint "eagle-import:SJW")
      (libsource (lib "eagle-import") (part "JUMPER"))
    )
    (comp (ref "SJ7")
      (value "JUMPER")
      (footprint "eagle-import:SJW")
      (libsource (lib "eagle-import") (part "JUMPER"))
    )
    (comp (ref "SJ8")
      (value "JUMPER")
      (footprint "eagle-import:SJW")
      (libsource (lib "eagle-import") (part "JUMPER"))
    )
    (comp (ref "SJ9")
      (value "JUMPER")
      (footprint "eagle-import:SJW")
      (libsource (lib "eagle-import") (part "JUMPER"))
    )
    (comp (ref "SJ10")
      (value "JUMPER")
      (footprint "eagle-import:SJW")
      (libsource (lib "eagle-import") (part "JUMPER"))
    )
    (comp (ref "SJ11")
      (value "JUMPER")
      (footprint "eagle-import:SJW")
      (libsource (lib "eagle-import") (part "JUMPER"))
    )
    (comp (ref "U$1")
      (value "PAM2306AYPKE")
      (footprint "eagle-import:WDFN_12L")
      (libsource (lib "eagle-import") (part "PAM2306AYPKE"))
    )
    (comp (ref "U$3")
      (value "MF-MSMF200")
      (footprint "eagle-import:MF-MSMF200")
      (libsource (lib "eagle-import") (part "MF-MSMF200"))
    )
    (comp (ref "U$4")
      (value "AP7115-25SEG")
      (footprint "eagle-import:SOT-25")
      (libsource (lib "eagle-import") (part "AP7115-25SEG"))
    )
    (comp (ref "U$5")
      (value "MIC5225")
      (footprint "eagle-import:SOT-25")
      (libsource (lib "eagle-import") (part "MIC5225"))
    )
  )
  (nets
    (net (code "1") (name "1V8") (class "Default")
      (node (ref "C6") (pin "1") (pinfunction "1_1") (pintype "passive"))
      (node (ref "C8") (pin "1") (pinfunction "1_1") (pintype "passive"))
      (node (ref "L2") (pin "2") (pinfunction "2_2") (pintype "passive"))
      (node (ref "SJ3") (pin "1") (pinfunction "1_1") (pintype "passive"))
      (node (ref "SJ8") (pin "2") (pinfunction "2_2") (pintype "passive"))
    )
    (net (code "2") (name "3V3") (class "Default")
      (node (ref "C28") (pin "1") (pinfunction "1_1") (pintype "passive"))
      (node (ref "C29") (pin "1") (pinfunction "1_1") (pintype "passive"))
      (node (ref "C31") (pin "1") (pinfunction "1_1") (pintype "passive"))
      (node (ref "C32") (pin "1") (pinfunction "1_1") (pintype "passive"))
      (node (ref "C5") (pin "1") (pinfunction "1_1") (pintype "passive"))
      (node (ref "C7") (pin "1") (pinfunction "1_1") (pintype "passive"))
      (node (ref "C9") (pin "1") (pinfunction "1_1") (pintype "passive"))
      (node (ref "L1") (pin "2") (pinfunction "2_2") (pintype "passive"))
      (node (ref "R6") (pin "2") (pinfunction "2_2") (pintype "passive"))
      (node (ref "SJ1") (pin "1") (pinfunction "1_1") (pintype "passive"))
      (node (ref "SJ2") (pin "1") (pinfunction "1_1") (pintype "passive"))
      (node (ref "SJ5") (pin "2") (pinfunction "2_2") (pintype "passive"))
      (node (ref "SJ6") (pin "1") (pinfunction "1_1") (pintype "passive"))
      (node (ref "SJ9") (pin "2") (pinfunction "2_2") (pintype "passive"))
      (node (ref "U$4") (pin "1") (pinfunction "VIN_1") (pintype "bidirectional"))
      (node (ref "U$4") (pin "3") (pinfunction "EN_3") (pintype "bidirectional"))
    )
    (net (code "3") (name "5V") (class "Default")
      (node (ref "C15") (pin "1") (pinfunction "1_1") (pintype "passive"))
      (node (ref "C3") (pin "1") (pinfunction "1_1") (pintype "passive"))
      (node (ref "C30") (pin "1") (pinfunction "1_1") (pintype "passive"))
      (node (ref "C4") (pin "1") (pinfunction "1_1") (pintype "passive"))
      (node (ref "J1") (pin "7") (pinfunction "7_7") (pintype "passive"))
      (node (ref "R1") (pin "2") (pinfunction "2_2") (pintype "passive"))
      (node (ref "SJ7") (pin "2") (pinfunction "2_2") (pintype "passive"))
      (node (ref "U$1") (pin "1") (pinfunction "VIN2_1") (pintype "bidirectional"))
      (node (ref "U$1") (pin "6") (pinfunction "EN1_6") (pintype "bidirectional"))
      (node (ref "U$1") (pin "7") (pinfunction "VIN1_7") (pintype "bidirectional"))
      (node (ref "U$3") (pin "P$2") (pinfunction "2_P$2") (pintype "passive"))
      (node (ref "U$5") (pin "1") (pinfunction "IN_1") (pintype "bidirectional"))
      (node (ref "U$5") (pin "3") (pinfunction "EN_3") (pintype "bidirectional"))
    )
    (net (code "4") (name "A") (class "Default")
      (node (ref "B17") (pin "1") (pinfunction "A_1") (pintype "bidirectional"))
      (node (ref "PCB1") (pin "66") (pinfunction "66/GPIO39_66") (pintype "bidirectional"))
    )
    (net (code "5") (name "B") (class "Default")
      (node (ref "B17") (pin "2") (pinfunction "B_2") (pintype "bidirectional"))
      (node (ref "PCB1") (pin "70") (pinfunction "70/GPIO40_70") (pintype "bidirectional"))
    )
    (net (code "6") (name "C") (class "Default")
      (node (ref "B17") (pin "3") (pinfunction "C_3") (pintype "bidirectional"))
      (node (ref "PCB1") (pin "72") (pinfunction "72/GPIO41_72") (pintype "bidirectional"))
    )
    (net (code "7") (name "CENTER") (class "Default")
      (node (ref "B17") (pin "6") (pinfunction "CENTER_6") (pintype "bidirectional"))
      (node (ref "PCB1") (pin "76") (pinfunction "76/GPIO42_76") (pintype "bidirectional"))
    )
    (net (code "8") (name "CM_1V8") (class "Default")
      (node (ref "C14") (pin "1") (pinfunction "1_1") (pintype "passive"))
      (node (ref "J1") (pin "3") (pinfunction "3_3") (pintype "passive"))
      (node (ref "PCB1") (pin "183") (pinfunction "183/1V8_183") (pintype "bidirectional"))
      (node (ref "PCB1") (pin "184") (pinfunction "184/1V8_184") (pintype "bidirectional"))
      (node (ref "PCB1") (pin "185") (pinfunction "185/1V8_185") (pintype "bidirectional"))
      (node (ref "PCB1") (pin "186") (pinfunction "186/1V8_186") (pintype "bidirectional"))
      (node (ref "SJ3") (pin "2") (pinfunction "2_2") (pintype "passive"))
    )
    (net (code "9") (name "CM_3V3") (class "Default")
      (node (ref "C13") (pin "1") (pinfunction "1_1") (pintype "passive"))
      (node (ref "J1") (pin "5") (pinfunction "5_5") (pintype "passive"))
      (node (ref "PCB1") (pin "191") (pinfunction "191/3V3_191") (pintype "bidirectional"))
      (node (ref "PCB1") (pin "192") (pinfunction "192/3V3_192") (pintype "bidirectional"))
      (node (ref "PCB1") (pin "193") (pinfunction "193/3V3_193") (pintype "bidirectional"))
      (node (ref "PCB1") (pin "194") (pinfunction "194/3V3_194") (pintype "bidirectional"))
      (node (ref "SJ2") (pin "2") (pinfunction "2_2") (pintype "passive"))
    )
    (net (code "10") (name "CM_VBAT") (class "Default")
      (node (ref "C12") (pin "1") (pinfunction "1_1") (pintype "passive"))
      (node (ref "J1") (pin "6") (pinfunction "6_6") (pintype "passive"))
      (node (ref "PCB1") (pin "197") (pinfunction "197/VBAT_197") (pintype "bidirectional"))
      (node (ref "PCB1") (pin "198") (pinfunction "198/VBAT_198") (pintype "bidirectional"))
      (node (ref "PCB1") (pin "199") (pinfunction "199/VBAT_199") (pintype "bidirectional"))
      (node (ref "PCB1") (pin "200") (pinfunction "200/VBAT_200") (pintype "bidirectional"))
      (node (ref "SJ1") (pin "2") (pinfunction "2_2") (pintype "passive"))
    )
    (net (code "11") (name "CM_VDAC") (class "Default")
      (node (ref "J1") (pin "4") (pinfunction "4_4") (pintype "passive"))
      (node (ref "PCB1") (pin "189") (pinfunction "189/VDAC_189") (pintype "bidirectional"))
      (node (ref "PCB1") (pin "190") (pinfunction "190/VDAC_190") (pintype "bidirectional"))
      (node (ref "SJ4") (pin "2") (pinfunction "2_2") (pintype "passive"))
    )
    (net (code "12") (name "COL_0") (class "Default")
      (node (ref "B1") (pin "B") (pinfunction "S_B") (pintype "passive"))
      (node (ref "B13") (pin "B") (pinfunction "S_B") (pintype "passive"))
      (node (ref "B19") (pin "B") (pinfunction "S_B") (pintype "passive"))
      (node (ref "B25") (pin "B") (pinfunction "S_B") (pintype "passive"))
      (node (ref "B31") (pin "B") (pinfunction "S_B") (pintype "passive"))
      (node (ref "B37") (pin "B") (pinfunction "S_B") (pintype "passive"))
      (node (ref "B43") (pin "B") (pinfunction "S_B") (pintype "passive"))
      (node (ref "B49") (pin "B") (pinfunction "S_B") (pintype "passive"))
      (node (ref "B55") (pin "B") (pinfunction "S_B") (pintype "passive"))
      (node (ref "B7") (pin "B") (pinfunction "S_B") (pintype "passive"))
      (node (ref "PCB1") (pin "69") (pinfunction "69/GPIO20_69") (pintype "bidirectional"))
    )
    (net (code "13") (name "COL_1") (class "Default")
      (node (ref "B14") (pin "B") (pinfunction "S_B") (pintype "passive"))
      (node (ref "B2") (pin "B") (pinfunction "S_B") (pintype "passive"))
      (node (ref "B20") (pin "B") (pinfunction "S_B") (pintype "passive"))
      (node (ref "B26") (pin "B") (pinfunction "S_B") (pintype "passive"))
      (node (ref "B32") (pin "B") (pinfunction "S_B") (pintype "passive"))
      (node (ref "B38") (pin "B") (pinfunction "S_B") (pintype "passive"))
      (node (ref "B44") (pin "B") (pinfunction "S_B") (pintype "passive"))
      (node (ref "B50") (pin "B") (pinfunction "S_B") (pintype "passive"))
      (node (ref "B56") (pin "B") (pinfunction "S_B") (pintype "passive"))
      (node (ref "B8") (pin "B") (pinfunction "S_B") (pintype "passive"))
      (node (ref "PCB1") (pin "71") (pinfunction "71/GPIO21_71") (pintype "bidirectional"))
    )
    (net (code "14") (name "COL_2") (class "Default")
      (node (ref "B15") (pin "B") (pinfunction "S_B") (pintype "passive"))
      (node (ref "B21") (pin "B") (pinfunction "S_B") (pintype "passive"))
      (node (ref "B27") (pin "B") (pinfunction "S_B") (pintype "passive"))
      (node (ref "B3") (pin "B") (pinfunction "S_B") (pintype "passive"))
      (node (ref "B33") (pin "B") (pinfunction "S_B") (pintype "passive"))
      (node (ref "B39") (pin "B") (pinfunction "S_B") (pintype "passive"))
      (node (ref "B45") (pin "B") (pinfunction "S_B") (pintype "passive"))
      (node (ref "B51") (pin "B") (pinfunction "S_B") (pintype "passive"))
      (node (ref "B57") (pin "B") (pinfunction "S_B") (pintype "passive"))
      (node (ref "B9") (pin "B") (pinfunction "S_B") (pintype "passive"))
      (node (ref "PCB1") (pin "75") (pinfunction "75/GPIO22_75") (pintype "bidirectional"))
    )
    (net (code "15") (name "COL_3") (class "Default")
      (node (ref "B10") (pin "B") (pinfunction "S_B") (pintype "passive"))
      (node (ref "B16") (pin "B") (pinfunction "S_B") (pintype "passive"))
      (node (ref "B22") (pin "B") (pinfunction "S_B") (pintype "passive"))
      (node (ref "B28") (pin "B") (pinfunction "S_B") (pintype "passive"))
      (node (ref "B34") (pin "B") (pinfunction "S_B") (pintype "passive"))
      (node (ref "B4") (pin "B") (pinfunction "S_B") (pintype "passive"))
      (node (ref "B40") (pin "B") (pinfunction "S_B") (pintype "passive"))
      (node (ref "B46") (pin "B") (pinfunction "S_B") (pintype "passive"))
      (node (ref "B52") (pin "B") (pinfunction "S_B") (pintype "passive"))
      (node (ref "B58") (pin "B") (pinfunction "S_B") (pintype "passive"))
      (node (ref "PCB1") (pin "77") (pinfunction "77/GPIO23_77") (pintype "bidirectional"))
    )
    (net (code "16") (name "COL_4") (class "Default")
      (node (ref "B11") (pin "B") (pinfunction "S_B") (pintype "passive"))
      (node (ref "B23") (pin "B") (pinfunction "S_B") (pintype "passive"))
      (node (ref "B29") (pin "B") (pinfunction "S_B") (pintype "passive"))
      (node (ref "B35") (pin "B") (pinfunction "S_B") (pintype "passive"))
      (node (ref "B41") (pin "B") (pinfunction "S_B") (pintype "passive"))
      (node (ref "B47") (pin "B") (pinfunction "S_B") (pintype "passive"))
      (node (ref "B5") (pin "B") (pinfunction "S_B") (pintype "passive"))
      (node (ref "B53") (pin "B") (pinfunction "S_B") (pintype "passive"))
      (node (ref "B59") (pin "B") (pinfunction "S_B") (pintype "passive"))
      (node (ref "PCB1") (pin "87") (pinfunction "87/GPIO26_87") (pintype "bidirectional"))
    )
    (net (code "17") (name "COL_5") (class "Default")
      (node (ref "B12") (pin "B") (pinfunction "S_B") (pintype "passive"))
      (node (ref "B18") (pin "B") (pinfunction "S_B") (pintype "passive"))
      (node (ref "B24") (pin "B") (pinfunction "S_B") (pintype "passive"))
      (node (ref "B30") (pin "B") (pinfunction "S_B") (pintype "passive"))
      (node (ref "B36") (pin "B") (pinfunction "S_B") (pintype "passive"))
      (node (ref "B42") (pin "B") (pinfunction "S_B") (pintype "passive"))
      (node (ref "B48") (pin "B") (pinfunction "S_B") (pintype "passive"))
      (node (ref "B54") (pin "B") (pinfunction "S_B") (pintype "passive"))
      (node (ref "B6") (pin "B") (pinfunction "S_B") (pintype "passive"))
      (node (ref "B60") (pin "B") (pinfunction "S_B") (pintype "passive"))
      (node (ref "PCB1") (pin "89") (pinfunction "89/GPIO27_89") (pintype "bidirectional"))
    )
    (net (code "18") (name "COMMON") (class "Default")
      (node (ref "B17") (pin "4") (pinfunction "COMMON_4") (pintype "bidirectional"))
      (node (ref "PCB1") (pin "134") (pinfunction "134/GND_134") (pintype "bidirectional"))
    )
    (net (code "19") (name "D") (class "Default")
      (node (ref "B17") (pin "5") (pinfunction "D_5") (pintype "bidirectional"))
      (node (ref "PCB1") (pin "78") (pinfunction "78/GPIO43_78") (pintype "bidirectional"))
    )
    (net (code "20") (name "DAC_2V5") (class "Default")
      (node (ref "C11") (pin "1") (pinfunction "1_1") (pintype "passive"))
      (node (ref "SJ4") (pin "1") (pinfunction "1_1") (pintype "passive"))
      (node (ref "U$4") (pin "5") (pinfunction "VOUT_5") (pintype "bidirectional"))
    )
    (net (code "21") (name "DCIN") (class "Default")
      (node (ref "JP1") (pin "1") (pinfunction "1_1") (pintype "passive"))
      (node (ref "U$3") (pin "P$1") (pinfunction "1_P$1") (pintype "passive"))
    )
    (net (code "22") (name "EMMC_DISABLE_N") (class "Default")
      (node (ref "PCB1") (pin "2") (pinfunction "2/EMMC_DISABLE_N_2") (pintype "bidirectional"))
    )
    (net (code "23") (name "GND") (class "Default")
      (node (ref "C1") (pin "2") (pinfunction "2_2") (pintype "passive"))
      (node (ref "C10") (pin "2") (pinfunction "2_2") (pintype "passive"))
      (node (ref "C11") (pin "2") (pinfunction "2_2") (pintype "passive"))
      (node (ref "C12") (pin "2") (pinfunction "2_2") (pintype "passive"))
      (node (ref "C13") (pin "2") (pinfunction "2_2") (pintype "passive"))
      (node (ref "C14") (pin "2") (pinfunction "2_2") (pintype "passive"))
      (node (ref "C15") (pin "2") (pinfunction "2_2") (pintype "passive"))
      (node (ref "C17") (pin "2") (pinfunction "2_2") (pintype "passive"))
      (node (ref "C2") (pin "2") (pinfunction "2_2") (pintype "passive"))
      (node (ref "C20") (pin "2") (pinfunction "2_2") (pintype "passive"))
      (node (ref "C21") (pin "2") (pinfunction "2_2") (pintype "passive"))
      (node (ref "C28") (pin "2") (pinfunction "2_2") (pintype "passive"))
      (node (ref "C29") (pin "2") (pinfunction "2_2") (pintype "passive"))
      (node (ref "C3") (pin "2") (pinfunction "2_2") (pintype "passive"))
      (node (ref "C30") (pin "2") (pinfunction "2_2") (pintype "passive"))
      (node (ref "C31") (pin "2") (pinfunction "2_2") (pintype "passive"))
      (node (ref "C32") (pin "2") (pinfunction "2_2") (pintype "passive"))
      (node (ref "C4") (pin "2") (pinfunction "2_2") (pintype "passive"))
      (node (ref "C5") (pin "2") (pinfunction "2_2") (pintype "passive"))
      (node (ref "C8") (pin "2") (pinfunction "2_2") (pintype "passive"))
      (node (ref "C9") (pin "2") (pinfunction "2_2") (pintype "passive"))
      (node (ref "IC1") (pin "1") (pinfunction "GND_1") (pintype "power_in"))
      (node (ref "J2") (pin "4") (pinfunction "4_4") (pintype "passive"))
      (node (ref "JP1") (pin "2") (pinfunction "2_2") (pintype "passive"))
      (node (ref "LED1") (pin "C") (pinfunction "C_C") (pintype "passive"))
      (node (ref "Q6") (pin "2") (pinfunction "E_2") (pintype "passive"))
      (node (ref "R13") (pin "2") (pinfunction "2_2") (pintype "passive"))
      (node (ref "R33") (pin "1") (pinfunction "1_1") (pintype "passive"))
      (node (ref "R34") (pin "1") (pinfunction "1_1") (pintype "passive"))
      (node (ref "R35") (pin "1") (pinfunction "1_1") (pintype "passive"))
      (node (ref "R36") (pin "1") (pinfunction "1_1") (pintype "passive"))
      (node (ref "R37") (pin "1") (pinfunction "1_1") (pintype "passive"))
      (node (ref "SJ10") (pin "1") (pinfunction "1_1") (pintype "passive"))
      (node (ref "SJ11") (pin "1") (pinfunction "1_1") (pintype "passive"))
      (node (ref "TFT1") (pin "43") (pinfunction "GND_43") (pintype "bidirectional"))
      (node (ref "TFT1") (pin "48") (pinfunction "GND_48") (pintype "bidirectional"))
      (node (ref "TFT1") (pin "49") (pinfunction "GND_49") (pintype "bidirectional"))
      (node (ref "TFT1") (pin "50") (pinfunction "GND_50") (pintype "bidirectional"))
      (node (ref "TFT1") (pin "6") (pinfunction "IM0_6") (pintype "bidirectional"))
      (node (ref "U$1") (pin "13") (pinfunction "PAD_13") (pintype "bidirectional"))
      (node (ref "U$1") (pin "3") (pinfunction "GND_3") (pintype "bidirectional"))
      (node (ref "U$1") (pin "9") (pinfunction "GND_9") (pintype "bidirectional"))
      (node (ref "U$4") (pin "2") (pinfunction "GND_2") (pintype "bidirectional"))
      (node (ref "U$5") (pin "2") (pinfunction "GND_2") (pintype "bidirectional"))
      (node (ref "UTSC") (pin "10") (pinfunction "GND_10") (pintype "bidirectional"))
    )
    (net (code "24") (name "GPIO0-27_VREF") (class "Default")
      (node (ref "C17") (pin "1") (pinfunction "1_1") (pintype "passive"))
      (node (ref "J1") (pin "2") (pinfunction "2_2") (pintype "passive"))
      (node (ref "PCB1") (pin "40") (pinfunction "40/GPIO0-27_VREF_40") (pintype "bidirectional"))
      (node (ref "SJ5") (pin "1") (pinfunction "1_1") (pintype "passive"))
    )
    (net (code "25") (name "GPIO28-45_VREF") (class "Default")
      (node (ref "C1") (pin "1") (pinfunction "1_1") (pintype "passive"))
      (node (ref "J1") (pin "1") (pinfunction "1_1") (pintype "passive"))
      (node (ref "PCB1") (pin "42") (pinfunction "42/GPIO28-45_VREF_42") (pintype "bidirectional"))
      (node (ref "SJ6") (pin "2") (pinfunction "2_2") (pintype "passive"))
    )
    (net (code "26") (name "GPIO46_1V8") (class "Default")
      (node (ref "PCB1") (pin "88") (pinfunction "88/GPIO46_1V8_88") (pintype "bidirectional"))
    )
    (net (code "27") (name "MISO") (class "Default")
      (node (ref "PCB1") (pin "29") (pinfunction "29/GPIO9_29") (pintype "bidirectional"))
      (node (ref "TFT1") (pin "33") (pinfunction "SDO_33") (pintype "bidirectional"))
      (node (ref "UTSC") (pin "3") (pinfunction "A0/DATA_OUT_3") (pintype "bidirectional"))
    )
    (net (code "28") (name "MOSI") (class "Default")
      (node (ref "PCB1") (pin "33") (pinfunction "33/GPIO10_33") (pintype "bidirectional"))
      (node (ref "R32") (pin "2") (pinfunction "2_2") (pintype "passive"))
      (node (ref "TFT1") (pin "34") (pinfunction "SDI_34") (pintype "bidirectional"))
      (node (ref "UTSC") (pin "7") (pinfunction "DATA_IN_7") (pintype "bidirectional"))
    )
    (net (code "29") (name "Net-(B1-P)") (class "Default")
      (node (ref "B1") (pin "A") (pinfunction "P_A") (pintype "passive"))
      (node (ref "D2") (pin "A") (pinfunction "A_A") (pintype "passive"))
    )
    (net (code "30") (name "Net-(B2-P)") (class "Default")
      (node (ref "B2") (pin "A") (pinfunction "P_A") (pintype "passive"))
      (node (ref "D3") (pin "A") (pinfunction "A_A") (pintype "passive"))
    )
    (net (code "31") (name "Net-(B3-P)") (class "Default")
      (node (ref "B3") (pin "A") (pinfunction "P_A") (pintype "passive"))
      (node (ref "D4") (pin "A") (pinfunction "A_A") (pintype "passive"))
    )
    (net (code "32") (name "Net-(B4-P)") (class "Default")
      (node (ref "B4") (pin "A") (pinfunction "P_A") (pintype "passive"))
      (node (ref "D5") (pin "A") (pinfunction "A_A") (pintype "passive"))
    )
    (net (code "33") (name "Net-(B5-P)") (class "Default")
      (node (ref "B5") (pin "A") (pinfunction "P_A") (pintype "passive"))
      (node (ref "D6") (pin "A") (pinfunction "A_A") (pintype "passive"))
    )
    (net (code "34") (name "Net-(B6-P)") (class "Default")
      (node (ref "B6") (pin "A") (pinfunction "P_A") (pintype "passive"))
      (node (ref "D7") (pin "A") (pinfunction "A_A") (pintype "passive"))
    )
    (net (code "35") (name "Net-(B7-P)") (class "Default")
      (node (ref "B7") (pin "A") (pinfunction "P_A") (pintype "passive"))
      (node (ref "D14") (pin "A") (pinfunction "A_A") (pintype "passive"))
    )
    (net (code "36") (name "Net-(B8-P)") (class "Default")
      (node (ref "B8") (pin "A") (pinfunction "P_A") (pintype "passive"))
      (node (ref "D15") (pin "A") (pinfunction "A_A") (pintype "passive"))
    )
    (net (code "37") (name "Net-(B9-P)") (class "Default")
      (node (ref "B9") (pin "A") (pinfunction "P_A") (pintype "passive"))
      (node (ref "D16") (pin "A") (pinfunction "A_A") (pintype "passive"))
    )
    (net (code "38") (name "Net-(B10-P)") (class "Default")
      (node (ref "B10") (pin "A") (pinfunction "P_A") (pintype "passive"))
      (node (ref "D17") (pin "A") (pinfunction "A_A") (pintype "passive"))
    )
    (net (code "39") (name "Net-(B11-P)") (class "Default")
      (node (ref "B11") (pin "A") (pinfunction "P_A") (pintype "passive"))
      (node (ref "D18") (pin "A") (pinfunction "A_A") (pintype "passive"))
    )
    (net (code "40") (name "Net-(B12-P)") (class "Default")
      (node (ref "B12") (pin "A") (pinfunction "P_A") (pintype "passive"))
      (node (ref "D19") (pin "A") (pinfunction "A_A") (pintype "passive"))
    )
    (net (code "41") (name "Net-(B13-P)") (class "Default")
      (node (ref "B13") (pin "A") (pinfunction "P_A") (pintype "passive"))
      (node (ref "D8") (pin "A") (pinfunction "A_A") (pintype "passive"))
    )
    (net (code "42") (name "Net-(B14-P)") (class "Default")
      (node (ref "B14") (pin "A") (pinfunction "P_A") (pintype "passive"))
      (node (ref "D9") (pin "A") (pinfunction "A_A") (pintype "passive"))
    )
    (net (code "43") (name "Net-(B15-P)") (class "Default")
      (node (ref "B15") (pin "A") (pinfunction "P_A") (pintype "passive"))
      (node (ref "D10") (pin "A") (pinfunction "A_A") (pintype "passive"))
    )
    (net (code "44") (name "Net-(B16-P)") (class "Default")
      (node (ref "B16") (pin "A") (pinfunction "P_A") (pintype "passive"))
      (node (ref "D11") (pin "A") (pinfunction "A_A") (pintype "passive"))
    )
    (net (code "45") (name "Net-(B18-P)") (class "Default")
      (node (ref "B18") (pin "A") (pinfunction "P_A") (pintype "passive"))
      (node (ref "D13") (pin "A") (pinfunction "A_A") (pintype "passive"))
    )
    (net (code "46") (name "Net-(B19-P)") (class "Default")
      (node (ref "B19") (pin "A") (pinfunction "P_A") (pintype "passive"))
      (node (ref "D20") (pin "A") (pinfunction "A_A") (pintype "passive"))
    )
    (net (code "47") (name "Net-(B20-P)") (class "Default")
      (node (ref "B20") (pin "A") (pinfunction "P_A") (pintype "passive"))
      (node (ref "D21") (pin "A") (pinfunction "A_A") (pintype "passive"))
    )
    (net (code "48") (name "Net-(B21-P)") (class "Default")
      (node (ref "B21") (pin "A") (pinfunction "P_A") (pintype "passive"))
      (node (ref "D22") (pin "A") (pinfunction "A_A") (pintype "passive"))
    )
    (net (code "49") (name "Net-(B22-P)") (class "Default")
      (node (ref "B22") (pin "A") (pinfunction "P_A") (pintype "passive"))
      (node (ref "D23") (pin "A") (pinfunction "A_A") (pintype "passive"))
    )
    (net (code "50") (name "Net-(B23-P)") (class "Default")
      (node (ref "B23") (pin "A") (pinfunction "P_A") (pintype "passive"))
      (node (ref "D24") (pin "A") (pinfunction "A_A") (pintype "passive"))
    )
    (net (code "51") (name "Net-(B24-P)") (class "Default")
      (node (ref "B24") (pin "A") (pinfunction "P_A") (pintype "passive"))
      (node (ref "D25") (pin "A") (pinfunction "A_A") (pintype "passive"))
    )
    (net (code "52") (name "Net-(B25-P)") (class "Default")
      (node (ref "B25") (pin "A") (pinfunction "P_A") (pintype "passive"))
      (node (ref "D26") (pin "A") (pinfunction "A_A") (pintype "passive"))
    )
    (net (code "53") (name "Net-(B26-P)") (class "Default")
      (node (ref "B26") (pin "A") (pinfunction "P_A") (pintype "passive"))
      (node (ref "D27") (pin "A") (pinfunction "A_A") (pintype "passive"))
    )
    (net (code "54") (name "Net-(B27-P)") (class "Default")
      (node (ref "B27") (pin "A") (pinfunction "P_A") (pintype "passive"))
      (node (ref "D28") (pin "A") (pinfunction "A_A") (pintype "passive"))
    )
    (net (code "55") (name "Net-(B28-P)") (class "Default")
      (node (ref "B28") (pin "A") (pinfunction "P_A") (pintype "passive"))
      (node (ref "D29") (pin "A") (pinfunction "A_A") (pintype "passive"))
    )
    (net (code "56") (name "Net-(B29-P)") (class "Default")
      (node (ref "B29") (pin "A") (pinfunction "P_A") (pintype "passive"))
      (node (ref "D30") (pin "A") (pinfunction "A_A") (pintype "passive"))
    )
    (net (code "57") (name "Net-(B30-P)") (class "Default")
      (node (ref "B30") (pin "A") (pinfunction "P_A") (pintype "passive"))
      (node (ref "D31") (pin "A") (pinfunction "A_A") (pintype "passive"))
    )
    (net (code "58") (name "Net-(B31-P)") (class "Default")
      (node (ref "B31") (pin "A") (pinfunction "P_A") (pintype "passive"))
      (node (ref "D32") (pin "A") (pinfunction "A_A") (pintype "passive"))
    )
    (net (code "59") (name "Net-(B32-P)") (class "Default")
      (node (ref "B32") (pin "A") (pinfunction "P_A") (pintype "passive"))
      (node (ref "D33") (pin "A") (pinfunction "A_A") (pintype "passive"))
    )
    (net (code "60") (name "Net-(B33-P)") (class "Default")
      (node (ref "B33") (pin "A") (pinfunction "P_A") (pintype "passive"))
      (node (ref "D34") (pin "A") (pinfunction "A_A") (pintype "passive"))
    )
    (net (code "61") (name "Net-(B34-P)") (class "Default")
      (node (ref "B34") (pin "A") (pinfunction "P_A") (pintype "passive"))
      (node (ref "D35") (pin "A") (pinfunction "A_A") (pintype "passive"))
    )
    (net (code "62") (name "Net-(B35-P)") (class "Default")
      (node (ref "B35") (pin "A") (pinfunction "P_A") (pintype "passive"))
      (node (ref "D36") (pin "A") (pinfunction "A_A") (pintype "passive"))
    )
    (net (code "63") (name "Net-(B36-P)") (class "Default")
      (node (ref "B36") (pin "A") (pinfunction "P_A") (pintype "passive"))
      (node (ref "D37") (pin "A") (pinfunction "A_A") (pintype "passive"))
    )
    (net (code "64") (name "Net-(B37-P)") (class "Default")
      (node (ref "B37") (pin "A") (pinfunction "P_A") (pintype "passive"))
      (node (ref "D38") (pin "A") (pinfunction "A_A") (pintype "passive"))
    )
    (net (code "65") (name "Net-(B38-P)") (class "Default")
      (node (ref "B38") (pin "A") (pinfunction "P_A") (pintype "passive"))
      (node (ref "D39") (pin "A") (pinfunction "A_A") (pintype "passive"))
    )
    (net (code "66") (name "Net-(B39-P)") (class "Default")
      (node (ref "B39") (pin "A") (pinfunction "P_A") (pintype "passive"))
      (node (ref "D40") (pin "A") (pinfunction "A_A") (pintype "passive"))
    )
    (net (code "67") (name "Net-(B40-P)") (class "Default")
      (node (ref "B40") (pin "A") (pinfunction "P_A") (pintype "passive"))
      (node (ref "D41") (pin "A") (pinfunction "A_A") (pintype "passive"))
    )
    (net (code "68") (name "Net-(B41-P)") (class "Default")
      (node (ref "B41") (pin "A") (pinfunction "P_A") (pintype "passive"))
      (node (ref "D42") (pin "A") (pinfunction "A_A") (pintype "passive"))
    )
    (net (code "69") (name "Net-(B42-P)") (class "Default")
      (node (ref "B42") (pin "A") (pinfunction "P_A") (pintype "passive"))
      (node (ref "D43") (pin "A") (pinfunction "A_A") (pintype "passive"))
    )
    (net (code "70") (name "Net-(B43-P)") (class "Default")
      (node (ref "B43") (pin "A") (pinfunction "P_A") (pintype "passive"))
      (node (ref "D44") (pin "A") (pinfunction "A_A") (pintype "passive"))
    )
    (net (code "71") (name "Net-(B44-P)") (class "Default")
      (node (ref "B44") (pin "A") (pinfunction "P_A") (pintype "passive"))
      (node (ref "D45") (pin "A") (pinfunction "A_A") (pintype "passive"))
    )
    (net (code "72") (name "Net-(B45-P)") (class "Default")
      (node (ref "B45") (pin "A") (pinfunction "P_A") (pintype "passive"))
      (node (ref "D46") (pin "A") (pinfunction "A_A") (pintype "passive"))
    )
    (net (code "73") (name "Net-(B46-P)") (class "Default")
      (node (ref "B46") (pin "A") (pinfunction "P_A") (pintype "passive"))
      (node (ref "D47") (pin "A") (pinfunction "A_A") (pintype "passive"))
    )
    (net (code "74") (name "Net-(B47-P)") (class "Default")
      (node (ref "B47") (pin "A") (pinfunction "P_A") (pintype "passive"))
      (node (ref "D48") (pin "A") (pinfunction "A_A") (pintype "passive"))
    )
    (net (code "75") (name "Net-(B48-P)") (class "Default")
      (node (ref "B48") (pin "A") (pinfunction "P_A") (pintype "passive"))
      (node (ref "D49") (pin "A") (pinfunction "A_A") (pintype "passive"))
    )
    (net (code "76") (name "Net-(B49-P)") (class "Default")
      (node (ref "B49") (pin "A") (pinfunction "P_A") (pintype "passive"))
      (node (ref "D50") (pin "A") (pinfunction "A_A") (pintype "passive"))
    )
    (net (code "77") (name "Net-(B50-P)") (class "Default")
      (node (ref "B50") (pin "A") (pinfunction "P_A") (pintype "passive"))
      (node (ref "D51") (pin "A") (pinfunction "A_A") (pintype "passive"))
    )
    (net (code "78") (name "Net-(B51-P)") (class "Default")
      (node (ref "B51") (pin "A") (pinfunction "P_A") (pintype "passive"))
      (node (ref "D52") (pin "A") (pinfunction "A_A") (pintype "passive"))
    )
    (net (code "79") (name "Net-(B52-P)") (class "Default")
      (node (ref "B52") (pin "A") (pinfunction "P_A") (pintype "passive"))
      (node (ref "D53") (pin "A") (pinfunction "A_A") (pintype "passive"))
    )
    (net (code "80") (name "Net-(B53-P)") (class "Default")
      (node (ref "B53") (pin "A") (pinfunction "P_A") (pintype "passive"))
      (node (ref "D54") (pin "A") (pinfunction "A_A") (pintype "passive"))
    )
    (net (code "81") (name "Net-(B54-P)") (class "Default")
      (node (ref "B54") (pin "A") (pinfunction "P_A") (pintype "passive"))
      (node (ref "D55") (pin "A") (pinfunction "A_A") (pintype "passive"))
    )
    (net (code "82") (name "Net-(B55-P)") (class "Default")
      (node (ref "B55") (pin "A") (pinfunction "P_A") (pintype "passive"))
      (node (ref "B55") (pin "A'") (pinfunction "P1_A'") (pintype "passive"))
      (node (ref "D56") (pin "A") (pinfunction "A_A") (pintype "passive"))
    )
    (net (code "83") (name "Net-(B56-P)") (class "Default")
      (node (ref "B56") (pin "A") (pinfunction "P_A") (pintype "passive"))
      (node (ref "B56") (pin "A'") (pinfunction "P1_A'") (pintype "passive"))
      (node (ref "D57") (pin "A") (pinfunction "A_A") (pintype "passive"))
    )
    (net (code "84") (name "Net-(B57-P)") (class "Default")
      (node (ref "B57") (pin "A") (pinfunction "P_A") (pintype "passive"))
      (node (ref "B57") (pin "A'") (pinfunction "P1_A'") (pintype "passive"))
      (node (ref "D58") (pin "A") (pinfunction "A_A") (pintype "passive"))
    )
    (net (code "85") (name "Net-(B58-P)") (class "Default")
      (node (ref "B58") (pin "A") (pinfunction "P_A") (pintype "passive"))
      (node (ref "B58") (pin "A'") (pinfunction "P1_A'") (pintype "passive"))
      (node (ref "D59") (pin "A") (pinfunction "A_A") (pintype "passive"))
    )
    (net (code "86") (name "Net-(B59-P)") (class "Default")
      (node (ref "B59") (pin "A") (pinfunction "P_A") (pintype "passive"))
      (node (ref "D60") (pin "A") (pinfunction "A_A") (pintype "passive"))
    )
    (net (code "87") (name "Net-(B60-P)") (class "Default")
      (node (ref "B60") (pin "A") (pinfunction "P_A") (pintype "passive"))
      (node (ref "D61") (pin "A") (pinfunction "A_A") (pintype "passive"))
    )
    (net (code "88") (name "Net-(IC1-{slash}RESET)") (class "Default")
      (node (ref "IC1") (pin "2") (pinfunction "/RESET_2") (pintype "output"))
      (node (ref "R16") (pin "1") (pinfunction "1_1") (pintype "passive"))
      (node (ref "TFT1") (pin "10") (pinfunction "RESET_10") (pintype "bidirectional"))
    )
    (net (code "89") (name "Net-(LED1-PadA)") (class "Default")
      (node (ref "LED1") (pin "A") (pinfunction "A_A") (pintype "passive"))
      (node (ref "R6") (pin "1") (pinfunction "1_1") (pintype "passive"))
    )
    (net (code "90") (name "Net-(PCB1-28{slash}GPIO28)") (class "Default")
      (node (ref "PCB1") (pin "28") (pinfunction "28/GPIO28_28") (pintype "bidirectional"))
      (node (ref "R34") (pin "2") (pinfunction "2_2") (pintype "passive"))
    )
    (net (code "91") (name "Net-(PCB1-30{slash}GPIO29)") (class "Default")
      (node (ref "PCB1") (pin "30") (pinfunction "30/GPIO29_30") (pintype "bidirectional"))
      (node (ref "R33") (pin "2") (pinfunction "2_2") (pintype "passive"))
    )
    (net (code "92") (name "Net-(PCB1-82{slash}GPIO44)") (class "Default")
      (node (ref "PCB1") (pin "82") (pinfunction "82/GPIO44_82") (pintype "bidirectional"))
      (node (ref "R36") (pin "2") (pinfunction "2_2") (pintype "passive"))
    )
    (net (code "93") (name "Net-(PCB1-84{slash}GPIO45)") (class "Default")
      (node (ref "PCB1") (pin "84") (pinfunction "84/GPIO45_84") (pintype "bidirectional"))
      (node (ref "R35") (pin "2") (pinfunction "2_2") (pintype "passive"))
    )
    (net (code "94") (name "Net-(PCB1-168{slash}USB_OTGID)") (class "Default")
      (node (ref "PCB1") (pin "168") (pinfunction "168/USB_OTGID_168") (pintype "bidirectional"))
      (node (ref "R37") (pin "2") (pinfunction "2_2") (pintype "passive"))
    )
    (net (code "95") (name "Net-(Q6-B)") (class "Default")
      (node (ref "Q6") (pin "1") (pinfunction "B_1") (pintype "passive"))
      (node (ref "R11") (pin "2") (pinfunction "2_2") (pintype "passive"))
    )
    (net (code "96") (name "Net-(Q6-C)") (class "Default")
      (node (ref "Q6") (pin "3") (pinfunction "C_3") (pintype "passive"))
      (node (ref "TFT1") (pin "1") (pinfunction "LEDK_1") (pintype "bidirectional"))
    )
    (net (code "97") (name "Net-(R27-Pad1)") (class "Default")
      (node (ref "R27") (pin "1") (pinfunction "1_1") (pintype "passive"))
      (node (ref "TFT1") (pin "2") (pinfunction "LEDA_2") (pintype "bidirectional"))
    )
    (net (code "98") (name "Net-(R28-Pad1)") (class "Default")
      (node (ref "R28") (pin "1") (pinfunction "1_1") (pintype "passive"))
      (node (ref "TFT1") (pin "3") (pinfunction "LEDA_3") (pintype "bidirectional"))
    )
    (net (code "99") (name "Net-(R29-Pad1)") (class "Default")
      (node (ref "R29") (pin "1") (pinfunction "1_1") (pintype "passive"))
      (node (ref "TFT1") (pin "4") (pinfunction "LEDA_4") (pintype "bidirectional"))
    )
    (net (code "100") (name "Net-(R30-Pad1)") (class "Default")
      (node (ref "R30") (pin "1") (pinfunction "1_1") (pintype "passive"))
      (node (ref "TFT1") (pin "5") (pinfunction "LEDA_5") (pintype "bidirectional"))
    )
    (net (code "101") (name "Net-(TFT1-DB0)") (class "Default")
      (node (ref "TFT1") (pin "15") (pinfunction "DB17_15") (pintype "bidirectional"))
      (node (ref "TFT1") (pin "16") (pinfunction "DB16_16") (pintype "bidirectional"))
      (node (ref "TFT1") (pin "17") (pinfunction "DB15_17") (pintype "bidirectional"))
      (node (ref "TFT1") (pin "18") (pinfunction "DB14_18") (pintype "bidirectional"))
      (node (ref "TFT1") (pin "19") (pinfunction "DB13_19") (pintype "bidirectional"))
      (node (ref "TFT1") (pin "20") (pinfunction "DB12_20") (pintype "bidirectional"))
      (node (ref "TFT1") (pin "21") (pinfunction "DB11_21") (pintype "bidirectional"))
      (node (ref "TFT1") (pin "22") (pinfunction "DB10_22") (pintype "bidirectional"))
      (node (ref "TFT1") (pin "23") (pinfunction "DB9_23") (pintype "bidirectional"))
      (node (ref "TFT1") (pin "24") (pinfunction "DB8_24") (pintype "bidirectional"))
      (node (ref "TFT1") (pin "25") (pinfunction "DB7_25") (pintype "bidirectional"))
      (node (ref "TFT1") (pin "26") (pinfunction "DB6_26") (pintype "bidirectional"))
      (node (ref "TFT1") (pin "27") (pinfunction "DB5_27") (pintype "bidirectional"))
      (node (ref "TFT1") (pin "28") (pinfunction "DB4_28") (pintype "bidirectional"))
      (node (ref "TFT1") (pin "29") (pinfunction "DB3_29") (pintype "bidirectional"))
      (node (ref "TFT1") (pin "30") (pinfunction "DB2_30") (pintype "bidirectional"))
      (node (ref "TFT1") (pin "31") (pinfunction "DB1_31") (pintype "bidirectional"))
      (node (ref "TFT1") (pin "32") (pinfunction "DB0_32") (pintype "bidirectional"))
    )
    (net (code "102") (name "Net-(U$1-EN2)") (class "Default")
      (node (ref "C2") (pin "1") (pinfunction "1_1") (pintype "passive"))
      (node (ref "R1") (pin "1") (pinfunction "1_1") (pintype "passive"))
      (node (ref "U$1") (pin "12") (pinfunction "EN2_12") (pintype "bidirectional"))
    )
    (net (code "103") (name "Net-(U$1-FB1)") (class "Default")
      (node (ref "C7") (pin "2") (pinfunction "2_2") (pintype "passive"))
      (node (ref "SJ11") (pin "2") (pinfunction "2_2") (pintype "passive"))
      (node (ref "SJ9") (pin "1") (pinfunction "1_1") (pintype "passive"))
      (node (ref "U$1") (pin "2") (pinfunction "FB1_2") (pintype "bidirectional"))
    )
    (net (code "104") (name "Net-(U$1-FB2)") (class "Default")
      (node (ref "C6") (pin "2") (pinfunction "2_2") (pintype "passive"))
      (node (ref "SJ10") (pin "2") (pinfunction "2_2") (pintype "passive"))
      (node (ref "SJ8") (pin "1") (pinfunction "1_1") (pintype "passive"))
      (node (ref "U$1") (pin "10") (pinfunction "FB2_10") (pintype "bidirectional"))
    )
    (net (code "105") (name "Net-(U$1-LX1)") (class "Default")
      (node (ref "L1") (pin "1") (pinfunction "1_1") (pintype "passive"))
      (node (ref "U$1") (pin "8") (pinfunction "LX1_8") (pintype "bidirectional"))
    )
    (net (code "106") (name "Net-(U$1-LX2)") (class "Default")
      (node (ref "L2") (pin "1") (pinfunction "1_1") (pintype "passive"))
      (node (ref "U$1") (pin "4") (pinfunction "LX2_4") (pintype "bidirectional"))
    )
    (net (code "107") (name "Net-(U$4-BYP)") (class "Default")
      (node (ref "C10") (pin "1") (pinfunction "1_1") (pintype "passive"))
      (node (ref "U$4") (pin "4") (pinfunction "BYP_4") (pintype "bidirectional"))
    )
    (net (code "108") (name "Net-(UTSC-IN2{slash}GPIO-2)") (class "Default")
      (node (ref "R11") (pin "1") (pinfunction "1_1") (pintype "passive"))
      (node (ref "R12") (pin "2") (pinfunction "2_2") (pintype "passive"))
      (node (ref "UTSC") (pin "11") (pinfunction "IN2/GPIO-2_11") (pintype "bidirectional"))
    )
    (net (code "109") (name "ROW_0") (class "Default")
      (node (ref "D2") (pin "C") (pinfunction "C_C") (pintype "passive"))
      (node (ref "D3") (pin "C") (pinfunction "C_C") (pintype "passive"))
      (node (ref "D4") (pin "C") (pinfunction "C_C") (pintype "passive"))
      (node (ref "D5") (pin "C") (pinfunction "C_C") (pintype "passive"))
      (node (ref "D6") (pin "C") (pinfunction "C_C") (pintype "passive"))
      (node (ref "D7") (pin "C") (pinfunction "C_C") (pintype "passive"))
      (node (ref "PCB1") (pin "3") (pinfunction "3/GPIO0_3") (pintype "bidirectional"))
    )
    (net (code "110") (name "ROW_1") (class "Default")
      (node (ref "D14") (pin "C") (pinfunction "C_C") (pintype "passive"))
      (node (ref "D15") (pin "C") (pinfunction "C_C") (pintype "passive"))
      (node (ref "D16") (pin "C") (pinfunction "C_C") (pintype "passive"))
      (node (ref "D17") (pin "C") (pinfunction "C_C") (pintype "passive"))
      (node (ref "D18") (pin "C") (pinfunction "C_C") (pintype "passive"))
      (node (ref "D19") (pin "C") (pinfunction "C_C") (pintype "passive"))
      (node (ref "PCB1") (pin "60") (pinfunction "60/GPIO37_60") (pintype "bidirectional"))
    )
    (net (code "111") (name "ROW_2") (class "Default")
      (node (ref "D10") (pin "C") (pinfunction "C_C") (pintype "passive"))
      (node (ref "D11") (pin "C") (pinfunction "C_C") (pintype "passive"))
      (node (ref "D13") (pin "C") (pinfunction "C_C") (pintype "passive"))
      (node (ref "D8") (pin "C") (pinfunction "C_C") (pintype "passive"))
      (node (ref "D9") (pin "C") (pinfunction "C_C") (pintype "passive"))
      (node (ref "PCB1") (pin "58") (pinfunction "58/GPIO36_58") (pintype "bidirectional"))
    )
    (net (code "112") (name "ROW_3") (class "Default")
      (node (ref "D20") (pin "C") (pinfunction "C_C") (pintype "passive"))
      (node (ref "D21") (pin "C") (pinfunction "C_C") (pintype "passive"))
      (node (ref "D22") (pin "C") (pinfunction "C_C") (pintype "passive"))
      (node (ref "D23") (pin "C") (pinfunction "C_C") (pintype "passive"))
      (node (ref "D24") (pin "C") (pinfunction "C_C") (pintype "passive"))
      (node (ref "D25") (pin "C") (pinfunction "C_C") (pintype "passive"))
      (node (ref "PCB1") (pin "54") (pinfunction "54/GPIO35_54") (pintype "bidirectional"))
    )
    (net (code "113") (name "ROW_4") (class "Default")
      (node (ref "D26") (pin "C") (pinfunction "C_C") (pintype "passive"))
      (node (ref "D27") (pin "C") (pinfunction "C_C") (pintype "passive"))
      (node (ref "D28") (pin "C") (pinfunction "C_C") (pintype "passive"))
      (node (ref "D29") (pin "C") (pinfunction "C_C") (pintype "passive"))
      (node (ref "D30") (pin "C") (pinfunction "C_C") (pintype "passive"))
      (node (ref "D31") (pin "C") (pinfunction "C_C") (pintype "passive"))
      (node (ref "PCB1") (pin "52") (pinfunction "52/GPIO34_52") (pintype "bidirectional"))
    )
    (net (code "114") (name "ROW_5") (class "Default")
      (node (ref "D32") (pin "C") (pinfunction "C_C") (pintype "passive"))
      (node (ref "D33") (pin "C") (pinfunction "C_C") (pintype "passive"))
      (node (ref "D34") (pin "C") (pinfunction "C_C") (pintype "passive"))
      (node (ref "D35") (pin "C") (pinfunction "C_C") (pintype "passive"))
      (node (ref "D36") (pin "C") (pinfunction "C_C") (pintype "passive"))
      (node (ref "D37") (pin "C") (pinfunction "C_C") (pintype "passive"))
      (node (ref "PCB1") (pin "48") (pinfunction "48/GPIO33_48") (pintype "bidirectional"))
    )
    (net (code "115") (name "ROW_6") (class "Default")
      (node (ref "D38") (pin "C") (pinfunction "C_C") (pintype "passive"))
      (node (ref "D39") (pin "C") (pinfunction "C_C") (pintype "passive"))
      (node (ref "D40") (pin "C") (pinfunction "C_C") (pintype "passive"))
      (node (ref "D41") (pin "C") (pinfunction "C_C") (pintype "passive"))
      (node (ref "D42") (pin "C") (pinfunction "C_C") (pintype "passive"))
      (node (ref "D43") (pin "C") (pinfunction "C_C") (pintype "passive"))
      (node (ref "PCB1") (pin "46") (pinfunction "46/GPIO32_46") (pintype "bidirectional"))
    )
    (net (code "116") (name "ROW_7") (class "Default")
      (node (ref "D44") (pin "C") (pinfunction "C_C") (pintype "passive"))
      (node (ref "D45") (pin "C") (pinfunction "C_C") (pintype "passive"))
      (node (ref "D46") (pin "C") (pinfunction "C_C") (pintype "passive"))
      (node (ref "D47") (pin "C") (pinfunction "C_C") (pintype "passive"))
      (node (ref "D48") (pin "C") (pinfunction "C_C") (pintype "passive"))
      (node (ref "D49") (pin "C") (pinfunction "C_C") (pintype "passive"))
      (node (ref "PCB1") (pin "36") (pinfunction "36/GPIO31_36") (pintype "bidirectional"))
    )
    (net (code "117") (name "ROW_8") (class "Default")
      (node (ref "D50") (pin "C") (pinfunction "C_C") (pintype "passive"))
      (node (ref "D51") (pin "C") (pinfunction "C_C") (pintype "passive"))
      (node (ref "D52") (pin "C") (pinfunction "C_C") (pintype "passive"))
      (node (ref "D53") (pin "C") (pinfunction "C_C") (pintype "passive"))
      (node (ref "D54") (pin "C") (pinfunction "C_C") (pintype "passive"))
      (node (ref "D55") (pin "C") (pinfunction "C_C") (pintype "passive"))
      (node (ref "PCB1") (pin "64") (pinfunction "64/GPIO38_64") (pintype "bidirectional"))
    )
    (net (code "118") (name "ROW_9") (class "Default")
      (node (ref "D56") (pin "C") (pinfunction "C_C") (pintype "passive"))
      (node (ref "D57") (pin "C") (pinfunction "C_C") (pintype "passive"))
      (node (ref "D58") (pin "C") (pinfunction "C_C") (pintype "passive"))
      (node (ref "D59") (pin "C") (pinfunction "C_C") (pintype "passive"))
      (node (ref "D60") (pin "C") (pinfunction "C_C") (pintype "passive"))
      (node (ref "D61") (pin "C") (pinfunction "C_C") (pintype "passive"))
      (node (ref "PCB1") (pin "5") (pinfunction "5/GPIO1_5") (pintype "bidirectional"))
    )
    (net (code "119") (name "RT_CS_3V") (class "Default")
      (node (ref "PCB1") (pin "23") (pinfunction "23/GPIO7_23") (pintype "bidirectional"))
      (node (ref "R14") (pin "2") (pinfunction "2_2") (pintype "passive"))
      (node (ref "UTSC") (pin "5") (pinfunction "SDAT_5") (pintype "bidirectional"))
    )
    (net (code "120") (name "RT_INT") (class "Default")
      (node (ref "PCB1") (pin "81") (pinfunction "81/GPIO24_81") (pintype "bidirectional"))
      (node (ref "R13") (pin "1") (pinfunction "1_1") (pintype "passive"))
      (node (ref "UTSC") (pin "2") (pinfunction "INTERRUPT_2") (pintype "bidirectional"))
    )
    (net (code "121") (name "SCLK") (class "Default")
      (node (ref "PCB1") (pin "35") (pinfunction "35/GPIO11_35") (pintype "bidirectional"))
      (node (ref "R31") (pin "2") (pinfunction "2_2") (pintype "passive"))
      (node (ref "TFT1") (pin "37") (pinfunction "RS_37") (pintype "bidirectional"))
      (node (ref "UTSC") (pin "4") (pinfunction "SCLK_4") (pintype "bidirectional"))
    )
    (net (code "122") (name "TFT_3V3") (class "Default")
      (node (ref "IC1") (pin "3") (pinfunction "VCC_3") (pintype "power_in"))
      (node (ref "R12") (pin "1") (pinfunction "1_1") (pintype "passive"))
      (node (ref "R14") (pin "1") (pinfunction "1_1") (pintype "passive"))
      (node (ref "R16") (pin "2") (pinfunction "2_2") (pintype "passive"))
      (node (ref "R27") (pin "2") (pinfunction "2_2") (pintype "passive"))
      (node (ref "R28") (pin "2") (pinfunction "2_2") (pintype "passive"))
      (node (ref "R29") (pin "2") (pinfunction "2_2") (pintype "passive"))
      (node (ref "R30") (pin "2") (pinfunction "2_2") (pintype "passive"))
      (node (ref "R31") (pin "1") (pinfunction "1_1") (pintype "passive"))
      (node (ref "R32") (pin "1") (pinfunction "1_1") (pintype "passive"))
      (node (ref "TFT1") (pin "40") (pinfunction "IOVCC_40") (pintype "bidirectional"))
      (node (ref "TFT1") (pin "41") (pinfunction "IOVCC_41") (pintype "bidirectional"))
      (node (ref "TFT1") (pin "42") (pinfunction "VCI_42") (pintype "bidirectional"))
      (node (ref "TFT1") (pin "7") (pinfunction "IM1_7") (pintype "bidirectional"))
      (node (ref "TFT1") (pin "8") (pinfunction "IM2_8") (pintype "bidirectional"))
      (node (ref "TFT1") (pin "9") (pinfunction "IM3_9") (pintype "bidirectional"))
      (node (ref "U$5") (pin "5") (pinfunction "OUT_5") (pintype "bidirectional"))
      (node (ref "UTSC") (pin "14") (pinfunction "VIO_14") (pintype "bidirectional"))
      (node (ref "UTSC") (pin "6") (pinfunction "VCC_6") (pintype "bidirectional"))
      (node (ref "UTSC") (pin "9") (pinfunction "IN1/GPIO-1/MODE_9") (pintype "bidirectional"))
    )
    (net (code "123") (name "TFT_CS_3V") (class "Default")
      (node (ref "PCB1") (pin "27") (pinfunction "27/GPIO8_27") (pintype "bidirectional"))
      (node (ref "TFT1") (pin "38") (pinfunction "#CS_38") (pintype "bidirectional"))
    )
    (net (code "124") (name "TFT_DC_3V") (class "Default")
      (node (ref "PCB1") (pin "83") (pinfunction "83/GPIO25_83") (pintype "bidirectional"))
      (node (ref "TFT1") (pin "36") (pinfunction "#WR_36") (pintype "bidirectional"))
    )
    (net (code "125") (name "USB_DM") (class "Default")
      (node (ref "J2") (pin "2") (pinfunction "2_2") (pintype "passive"))
      (node (ref "PCB1") (pin "165") (pinfunction "165/USB_DP**_165") (pintype "bidirectional"))
    )
    (net (code "126") (name "USB_DP") (class "Default")
      (node (ref "J2") (pin "3") (pinfunction "3_3") (pintype "passive"))
      (node (ref "PCB1") (pin "167") (pinfunction "167/USB_DM**_167") (pintype "bidirectional"))
    )
    (net (code "127") (name "VBUSA") (class "Default")
      (node (ref "C20") (pin "1") (pinfunction "1_1") (pintype "passive"))
      (node (ref "C21") (pin "1") (pinfunction "1_1") (pintype "passive"))
      (node (ref "J2") (pin "1") (pinfunction "1_1") (pintype "passive"))
      (node (ref "SJ7") (pin "1") (pinfunction "1_1") (pintype "passive"))
    )
    (net (code "128") (name "X+") (class "Default")
      (node (ref "TFT1") (pin "44") (pinfunction "XR_44") (pintype "bidirectional"))
      (node (ref "UTSC") (pin "13") (pinfunction "X+_13") (pintype "bidirectional"))
    )
    (net (code "129") (name "X-") (class "Default")
      (node (ref "TFT1") (pin "46") (pinfunction "XL_46") (pintype "bidirectional"))
      (node (ref "UTSC") (pin "16") (pinfunction "X-_16") (pintype "bidirectional"))
    )
    (net (code "130") (name "Y+") (class "Default")
      (node (ref "TFT1") (pin "47") (pinfunction "YU_47") (pintype "bidirectional"))
      (node (ref "UTSC") (pin "15") (pinfunction "Y+_15") (pintype "bidirectional"))
    )
    (net (code "131") (name "Y-") (class "Default")
      (node (ref "TFT1") (pin "45") (pinfunction "YD_45") (pintype "bidirectional"))
      (node (ref "UTSC") (pin "1") (pinfunction "Y-_1") (pintype "bidirectional"))
    )
    (net (code "132") (name "unconnected-(B1-P1-PadA')") (class "Default")
      (node (ref "B1") (pin "A'") (pinfunction "P1_A'") (pintype "passive"))
    )
    (net (code "133") (name "unconnected-(B1-S1-PadB')") (class "Default")
      (node (ref "B1") (pin "B'") (pinfunction "S1_B'") (pintype "passive"))
    )
    (net (code "134") (name "unconnected-(B2-P1-PadA')") (class "Default")
      (node (ref "B2") (pin "A'") (pinfunction "P1_A'") (pintype "passive"))
    )
    (net (code "135") (name "unconnected-(B2-S1-PadB')") (class "Default")
      (node (ref "B2") (pin "B'") (pinfunction "S1_B'") (pintype "passive"))
    )
    (net (code "136") (name "unconnected-(B3-P1-PadA')") (class "Default")
      (node (ref "B3") (pin "A'") (pinfunction "P1_A'") (pintype "passive"))
    )
    (net (code "137") (name "unconnected-(B3-S1-PadB')") (class "Default")
      (node (ref "B3") (pin "B'") (pinfunction "S1_B'") (pintype "passive"))
    )
    (net (code "138") (name "unconnected-(B4-P1-PadA')") (class "Default")
      (node (ref "B4") (pin "A'") (pinfunction "P1_A'") (pintype "passive"))
    )
    (net (code "139") (name "unconnected-(B4-S1-PadB')") (class "Default")
      (node (ref "B4") (pin "B'") (pinfunction "S1_B'") (pintype "passive"))
    )
    (net (code "140") (name "unconnected-(B5-P1-PadA')") (class "Default")
      (node (ref "B5") (pin "A'") (pinfunction "P1_A'") (pintype "passive"))
    )
    (net (code "141") (name "unconnected-(B5-S1-PadB')") (class "Default")
      (node (ref "B5") (pin "B'") (pinfunction "S1_B'") (pintype "passive"))
    )
    (net (code "142") (name "unconnected-(B6-P1-PadA')") (class "Default")
      (node (ref "B6") (pin "A'") (pinfunction "P1_A'") (pintype "passive"))
    )
    (net (code "143") (name "unconnected-(B6-S1-PadB')") (class "Default")
      (node (ref "B6") (pin "B'") (pinfunction "S1_B'") (pintype "passive"))
    )
    (net (code "144") (name "unconnected-(B7-P1-PadA')") (class "Default")
      (node (ref "B7") (pin "A'") (pinfunction "P1_A'") (pintype "passive"))
    )
    (net (code "145") (name "unconnected-(B7-S1-PadB')") (class "Default")
      (node (ref "B7") (pin "B'") (pinfunction "S1_B'") (pintype "passive"))
    )
    (net (code "146") (name "unconnected-(B8-P1-PadA')") (class "Default")
      (node (ref "B8") (pin "A'") (pinfunction "P1_A'") (pintype "passive"))
    )
    (net (code "147") (name "unconnected-(B8-S1-PadB')") (class "Default")
      (node (ref "B8") (pin "B'") (pinfunction "S1_B'") (pintype "passive"))
    )
    (net (code "148") (name "unconnected-(B9-P1-PadA')") (class "Default")
      (node (ref "B9") (pin "A'") (pinfunction "P1_A'") (pintype "passive"))
    )
    (net (code "149") (name "unconnected-(B9-S1-PadB')") (class "Default")
      (node (ref "B9") (pin "B'") (pinfunction "S1_B'") (pintype "passive"))
    )
    (net (code "150") (name "unconnected-(B10-P1-PadA')") (class "Default")
      (node (ref "B10") (pin "A'") (pinfunction "P1_A'") (pintype "passive"))
    )
    (net (code "151") (name "unconnected-(B10-S1-PadB')") (class "Default")
      (node (ref "B10") (pin "B'") (pinfunction "S1_B'") (pintype "passive"))
    )
    (net (code "152") (name "unconnected-(B11-P1-PadA')") (class "Default")
      (node (ref "B11") (pin "A'") (pinfunction "P1_A'") (pintype "passive"))
    )
    (net (code "153") (name "unconnected-(B11-S1-PadB')") (class "Default")
      (node (ref "B11") (pin "B'") (pinfunction "S1_B'") (pintype "passive"))
    )
    (net (code "154") (name "unconnected-(B12-P1-PadA')") (class "Default")
      (node (ref "B12") (pin "A'") (pinfunction "P1_A'") (pintype "passive"))
    )
    (net (code "155") (name "unconnected-(B12-S1-PadB')") (class "Default")
      (node (ref "B12") (pin "B'") (pinfunction "S1_B'") (pintype "passive"))
    )
    (net (code "156") (name "unconnected-(B13-P1-PadA')") (class "Default")
      (node (ref "B13") (pin "A'") (pinfunction "P1_A'") (pintype "passive"))
    )
    (net (code "157") (name "unconnected-(B13-S1-PadB')") (class "Default")
      (node (ref "B13") (pin "B'") (pinfunction "S1_B'") (pintype "passive"))
    )
    (net (code "158") (name "unconnected-(B14-P1-PadA')") (class "Default")
      (node (ref "B14") (pin "A'") (pinfunction "P1_A'") (pintype "passive"))
    )
    (net (code "159") (name "unconnected-(B14-S1-PadB')") (class "Default")
      (node (ref "B14") (pin "B'") (pinfunction "S1_B'") (pintype "passive"))
    )
    (net (code "160") (name "unconnected-(B15-P1-PadA')") (class "Default")
      (node (ref "B15") (pin "A'") (pinfunction "P1_A'") (pintype "passive"))
    )
    (net (code "161") (name "unconnected-(B15-S1-PadB')") (class "Default")
      (node (ref "B15") (pin "B'") (pinfunction "S1_B'") (pintype "passive"))
    )
    (net (code "162") (name "unconnected-(B16-P1-PadA')") (class "Default")
      (node (ref "B16") (pin "A'") (pinfunction "P1_A'") (pintype "passive"))
    )
    (net (code "163") (name "unconnected-(B16-S1-PadB')") (class "Default")
      (node (ref "B16") (pin "B'") (pinfunction "S1_B'") (pintype "passive"))
    )
    (net (code "164") (name "unconnected-(B18-P1-PadA')") (class "Default")
      (node (ref "B18") (pin "A'") (pinfunction "P1_A'") (pintype "passive"))
    )
    (net (code "165") (name "unconnected-(B18-S1-PadB')") (class "Default")
      (node (ref "B18") (pin "B'") (pinfunction "S1_B'") (pintype "passive"))
    )
    (net (code "166") (name "unconnected-(B19-P1-PadA')") (class "Default")
      (node (ref "B19") (pin "A'") (pinfunction "P1_A'") (pintype "passive"))
    )
    (net (code "167") (name "unconnected-(B19-S1-PadB')") (class "Default")
      (node (ref "B19") (pin "B'") (pinfunction "S1_B'") (pintype "passive"))
    )
    (net (code "168") (name "unconnected-(B20-P1-PadA')") (class "Default")
      (node (ref "B20") (pin "A'") (pinfunction "P1_A'") (pintype "passive"))
    )
    (net (code "169") (name "unconnected-(B20-S1-PadB')") (class "Default")
      (node (ref "B20") (pin "B'") (pinfunction "S1_B'") (pintype "passive"))
    )
    (net (code "170") (name "unconnected-(B21-P1-PadA')") (class "Default")
      (node (ref "B21") (pin "A'") (pinfunction "P1_A'") (pintype "passive"))
    )
    (net (code "171") (name "unconnected-(B21-S1-PadB')") (class "Default")
      (node (ref "B21") (pin "B'") (pinfunction "S1_B'") (pintype "passive"))
    )
    (net (code "172") (name "unconnected-(B22-P1-PadA')") (class "Default")
      (node (ref "B22") (pin "A'") (pinfunction "P1_A'") (pintype "passive"))
    )
    (net (code "173") (name "unconnected-(B22-S1-PadB')") (class "Default")
      (node (ref "B22") (pin "B'") (pinfunction "S1_B'") (pintype "passive"))
    )
    (net (code "174") (name "unconnected-(B23-P1-PadA')") (class "Default")
      (node (ref "B23") (pin "A'") (pinfunction "P1_A'") (pintype "passive"))
    )
    (net (code "175") (name "unconnected-(B23-S1-PadB')") (class "Default")
      (node (ref "B23") (pin "B'") (pinfunction "S1_B'") (pintype "passive"))
    )
    (net (code "176") (name "unconnected-(B24-P1-PadA')") (class "Default")
      (node (ref "B24") (pin "A'") (pinfunction "P1_A'") (pintype "passive"))
    )
    (net (code "177") (name "unconnected-(B24-S1-PadB')") (class "Default")
      (node (ref "B24") (pin "B'") (pinfunction "S1_B'") (pintype "passive"))
    )
    (net (code "178") (name "unconnected-(B25-P1-PadA')") (class "Default")
      (node (ref "B25") (pin "A'") (pinfunction "P1_A'") (pintype "passive"))
    )
    (net (code "179") (name "unconnected-(B25-S1-PadB')") (class "Default")
      (node (ref "B25") (pin "B'") (pinfunction "S1_B'") (pintype "passive"))
    )
    (net (code "180") (name "unconnected-(B26-P1-PadA')") (class "Default")
      (node (ref "B26") (pin "A'") (pinfunction "P1_A'") (pintype "passive"))
    )
    (net (code "181") (name "unconnected-(B26-S1-PadB')") (class "Default")
      (node (ref "B26") (pin "B'") (pinfunction "S1_B'") (pintype "passive"))
    )
    (net (code "182") (name "unconnected-(B27-P1-PadA')") (class "Default")
      (node (ref "B27") (pin "A'") (pinfunction "P1_A'") (pintype "passive"))
    )
    (net (code "183") (name "unconnected-(B27-S1-PadB')") (class "Default")
      (node (ref "B27") (pin "B'") (pinfunction "S1_B'") (pintype "passive"))
    )
    (net (code "184") (name "unconnected-(B28-P1-PadA')") (class "Default")
      (node (ref "B28") (pin "A'") (pinfunction "P1_A'") (pintype "passive"))
    )
    (net (code "185") (name "unconnected-(B28-S1-PadB')") (class "Default")
      (node (ref "B28") (pin "B'") (pinfunction "S1_B'") (pintype "passive"))
    )
    (net (code "186") (name "unconnected-(B29-P1-PadA')") (class "Default")
      (node (ref "B29") (pin "A'") (pinfunction "P1_A'") (pintype "passive"))
    )
    (net (code "187") (name "unconnected-(B29-S1-PadB')") (class "Default")
      (node (ref "B29") (pin "B'") (pinfunction "S1_B'") (pintype "passive"))
    )
    (net (code "188") (name "unconnected-(B30-P1-PadA')") (class "Default")
      (node (ref "B30") (pin "A'") (pinfunction "P1_A'") (pintype "passive"))
    )
    (net (code "189") (name "unconnected-(B30-S1-PadB')") (class "Default")
      (node (ref "B30") (pin "B'") (pinfunction "S1_B'") (pintype "passive"))
    )
    (net (code "190") (name "unconnected-(B31-P1-PadA')") (class "Default")
      (node (ref "B31") (pin "A'") (pinfunction "P1_A'") (pintype "passive"))
    )
    (net (code "191") (name "unconnected-(B31-S1-PadB')") (class "Default")
      (node (ref "B31") (pin "B'") (pinfunction "S1_B'") (pintype "passive"))
    )
    (net (code "192") (name "unconnected-(B32-P1-PadA')") (class "Default")
      (node (ref "B32") (pin "A'") (pinfunction "P1_A'") (pintype "passive"))
    )
    (net (code "193") (name "unconnected-(B32-S1-PadB')") (class "Default")
      (node (ref "B32") (pin "B'") (pinfunction "S1_B'") (pintype "passive"))
    )
    (net (code "194") (name "unconnected-(B33-P1-PadA')") (class "Default")
      (node (ref "B33") (pin "A'") (pinfunction "P1_A'") (pintype "passive"))
    )
    (net (code "195") (name "unconnected-(B33-S1-PadB')") (class "Default")
      (node (ref "B33") (pin "B'") (pinfunction "S1_B'") (pintype "passive"))
    )
    (net (code "196") (name "unconnected-(B34-P1-PadA')") (class "Default")
      (node (ref "B34") (pin "A'") (pinfunction "P1_A'") (pintype "passive"))
    )
    (net (code "197") (name "unconnected-(B34-S1-PadB')") (class "Default")
      (node (ref "B34") (pin "B'") (pinfunction "S1_B'") (pintype "passive"))
    )
    (net (code "198") (name "unconnected-(B35-P1-PadA')") (class "Default")
      (node (ref "B35") (pin "A'") (pinfunction "P1_A'") (pintype "passive"))
    )
    (net (code "199") (name "unconnected-(B35-S1-PadB')") (class "Default")
      (node (ref "B35") (pin "B'") (pinfunction "S1_B'") (pintype "passive"))
    )
    (net (code "200") (name "unconnected-(B36-P1-PadA')") (class "Default")
      (node (ref "B36") (pin "A'") (pinfunction "P1_A'") (pintype "passive"))
    )
    (net (code "201") (name "unconnected-(B36-S1-PadB')") (class "Default")
      (node (ref "B36") (pin "B'") (pinfunction "S1_B'") (pintype "passive"))
    )
    (net (code "202") (name "unconnected-(B37-P1-PadA')") (class "Default")
      (node (ref "B37") (pin "A'") (pinfunction "P1_A'") (pintype "passive"))
    )
    (net (code "203") (name "unconnected-(B37-S1-PadB')") (class "Default")
      (node (ref "B37") (pin "B'") (pinfunction "S1_B'") (pintype "passive"))
    )
    (net (code "204") (name "unconnected-(B38-P1-PadA')") (class "Default")
      (node (ref "B38") (pin "A'") (pinfunction "P1_A'") (pintype "passive"))
    )
    (net (code "205") (name "unconnected-(B38-S1-PadB')") (class "Default")
      (node (ref "B38") (pin "B'") (pinfunction "S1_B'") (pintype "passive"))
    )
    (net (code "206") (name "unconnected-(B39-P1-PadA')") (class "Default")
      (node (ref "B39") (pin "A'") (pinfunction "P1_A'") (pintype "passive"))
    )
    (net (code "207") (name "unconnected-(B39-S1-PadB')") (class "Default")
      (node (ref "B39") (pin "B'") (pinfunction "S1_B'") (pintype "passive"))
    )
    (net (code "208") (name "unconnected-(B40-P1-PadA')") (class "Default")
      (node (ref "B40") (pin "A'") (pinfunction "P1_A'") (pintype "passive"))
    )
    (net (code "209") (name "unconnected-(B40-S1-PadB')") (class "Default")
      (node (ref "B40") (pin "B'") (pinfunction "S1_B'") (pintype "passive"))
    )
    (net (code "210") (name "unconnected-(B41-P1-PadA')") (class "Default")
      (node (ref "B41") (pin "A'") (pinfunction "P1_A'") (pintype "passive"))
    )
    (net (code "211") (name "unconnected-(B41-S1-PadB')") (class "Default")
      (node (ref "B41") (pin "B'") (pinfunction "S1_B'") (pintype "passive"))
    )
    (net (code "212") (name "unconnected-(B42-P1-PadA')") (class "Default")
      (node (ref "B42") (pin "A'") (pinfunction "P1_A'") (pintype "passive"))
    )
    (net (code "213") (name "unconnected-(B42-S1-PadB')") (class "Default")
      (node (ref "B42") (pin "B'") (pinfunction "S1_B'") (pintype "passive"))
    )
    (net (code "214") (name "unconnected-(B43-P1-PadA')") (class "Default")
      (node (ref "B43") (pin "A'") (pinfunction "P1_A'") (pintype "passive"))
    )
    (net (code "215") (name "unconnected-(B43-S1-PadB')") (class "Default")
      (node (ref "B43") (pin "B'") (pinfunction "S1_B'") (pintype "passive"))
    )
    (net (code "216") (name "unconnected-(B44-P1-PadA')") (class "Default")
      (node (ref "B44") (pin "A'") (pinfunction "P1_A'") (pintype "passive"))
    )
    (net (code "217") (name "unconnected-(B44-S1-PadB')") (class "Default")
      (node (ref "B44") (pin "B'") (pinfunction "S1_B'") (pintype "passive"))
    )
    (net (code "218") (name "unconnected-(B45-P1-PadA')") (class "Default")
      (node (ref "B45") (pin "A'") (pinfunction "P1_A'") (pintype "passive"))
    )
    (net (code "219") (name "unconnected-(B45-S1-PadB')") (class "Default")
      (node (ref "B45") (pin "B'") (pinfunction "S1_B'") (pintype "passive"))
    )
    (net (code "220") (name "unconnected-(B46-P1-PadA')") (class "Default")
      (node (ref "B46") (pin "A'") (pinfunction "P1_A'") (pintype "passive"))
    )
    (net (code "221") (name "unconnected-(B46-S1-PadB')") (class "Default")
      (node (ref "B46") (pin "B'") (pinfunction "S1_B'") (pintype "passive"))
    )
    (net (code "222") (name "unconnected-(B47-P1-PadA')") (class "Default")
      (node (ref "B47") (pin "A'") (pinfunction "P1_A'") (pintype "passive"))
    )
    (net (code "223") (name "unconnected-(B47-S1-PadB')") (class "Default")
      (node (ref "B47") (pin "B'") (pinfunction "S1_B'") (pintype "passive"))
    )
    (net (code "224") (name "unconnected-(B48-P1-PadA')") (class "Default")
      (node (ref "B48") (pin "A'") (pinfunction "P1_A'") (pintype "passive"))
    )
    (net (code "225") (name "unconnected-(B48-S1-PadB')") (class "Default")
      (node (ref "B48") (pin "B'") (pinfunction "S1_B'") (pintype "passive"))
    )
    (net (code "226") (name "unconnected-(B49-P1-PadA')") (class "Default")
      (node (ref "B49") (pin "A'") (pinfunction "P1_A'") (pintype "passive"))
    )
    (net (code "227") (name "unconnected-(B49-S1-PadB')") (class "Default")
      (node (ref "B49") (pin "B'") (pinfunction "S1_B'") (pintype "passive"))
    )
    (net (code "228") (name "unconnected-(B50-P1-PadA')") (class "Default")
      (node (ref "B50") (pin "A'") (pinfunction "P1_A'") (pintype "passive"))
    )
    (net (code "229") (name "unconnected-(B50-S1-PadB')") (class "Default")
      (node (ref "B50") (pin "B'") (pinfunction "S1_B'") (pintype "passive"))
    )
    (net (code "230") (name "unconnected-(B51-P1-PadA')") (class "Default")
      (node (ref "B51") (pin "A'") (pinfunction "P1_A'") (pintype "passive"))
    )
    (net (code "231") (name "unconnected-(B51-S1-PadB')") (class "Default")
      (node (ref "B51") (pin "B'") (pinfunction "S1_B'") (pintype "passive"))
    )
    (net (code "232") (name "unconnected-(B52-P1-PadA')") (class "Default")
      (node (ref "B52") (pin "A'") (pinfunction "P1_A'") (pintype "passive"))
    )
    (net (code "233") (name "unconnected-(B52-S1-PadB')") (class "Default")
      (node (ref "B52") (pin "B'") (pinfunction "S1_B'") (pintype "passive"))
    )
    (net (code "234") (name "unconnected-(B53-P1-PadA')") (class "Default")
      (node (ref "B53") (pin "A'") (pinfunction "P1_A'") (pintype "passive"))
    )
    (net (code "235") (name "unconnected-(B53-S1-PadB')") (class "Default")
      (node (ref "B53") (pin "B'") (pinfunction "S1_B'") (pintype "passive"))
    )
    (net (code "236") (name "unconnected-(B54-P1-PadA')") (class "Default")
      (node (ref "B54") (pin "A'") (pinfunction "P1_A'") (pintype "passive"))
    )
    (net (code "237") (name "unconnected-(B54-S1-PadB')") (class "Default")
      (node (ref "B54") (pin "B'") (pinfunction "S1_B'") (pintype "passive"))
    )
    (net (code "238") (name "unconnected-(B55-S1-PadB')") (class "Default")
      (node (ref "B55") (pin "B'") (pinfunction "S1_B'") (pintype "passive"))
    )
    (net (code "239") (name "unconnected-(B56-S1-PadB')") (class "Default")
      (node (ref "B56") (pin "B'") (pinfunction "S1_B'") (pintype "passive"))
    )
    (net (code "240") (name "unconnected-(B57-S1-PadB')") (class "Default")
      (node (ref "B57") (pin "B'") (pinfunction "S1_B'") (pintype "passive"))
    )
    (net (code "241") (name "unconnected-(B58-S1-PadB')") (class "Default")
      (node (ref "B58") (pin "B'") (pinfunction "S1_B'") (pintype "passive"))
    )
    (net (code "242") (name "unconnected-(B59-P1-PadA')") (class "Default")
      (node (ref "B59") (pin "A'") (pinfunction "P1_A'") (pintype "passive"))
    )
    (net (code "243") (name "unconnected-(B59-S1-PadB')") (class "Default")
      (node (ref "B59") (pin "B'") (pinfunction "S1_B'") (pintype "passive"))
    )
    (net (code "244") (name "unconnected-(B60-P1-PadA')") (class "Default")
      (node (ref "B60") (pin "A'") (pinfunction "P1_A'") (pintype "passive"))
    )
    (net (code "245") (name "unconnected-(B60-S1-PadB')") (class "Default")
      (node (ref "B60") (pin "B'") (pinfunction "S1_B'") (pintype "passive"))
    )
    (net (code "246") (name "unconnected-(JP1-Pad3)") (class "Default")
      (node (ref "JP1") (pin "3") (pinfunction "3_3") (pintype "passive"))
    )
    (net (code "247") (name "unconnected-(PCB1-1{slash}GND-Pad1)") (class "Default")
      (node (ref "PCB1") (pin "1") (pinfunction "1/GND_1") (pintype "bidirectional"))
    )
    (net (code "248") (name "unconnected-(PCB1-4{slash}NC-Pad4)") (class "Default")
      (node (ref "PCB1") (pin "4") (pinfunction "4/NC_4") (pintype "bidirectional"))
    )
    (net (code "249") (name "unconnected-(PCB1-6{slash}NC-Pad6)") (class "Default")
      (node (ref "PCB1") (pin "6") (pinfunction "6/NC_6") (pintype "bidirectional"))
    )
    (net (code "250") (name "unconnected-(PCB1-7{slash}GND-Pad7)") (class "Default")
      (node (ref "PCB1") (pin "7") (pinfunction "7/GND_7") (pintype "bidirectional"))
    )
    (net (code "251") (name "unconnected-(PCB1-8{slash}NC-Pad8)") (class "Default")
      (node (ref "PCB1") (pin "8") (pinfunction "8/NC_8") (pintype "bidirectional"))
    )
    (net (code "252") (name "unconnected-(PCB1-9{slash}GPIO2-Pad9)") (class "Default")
      (node (ref "PCB1") (pin "9") (pinfunction "9/GPIO2_9") (pintype "bidirectional"))
    )
    (net (code "253") (name "unconnected-(PCB1-10{slash}NC-Pad10)") (class "Default")
      (node (ref "PCB1") (pin "10") (pinfunction "10/NC_10") (pintype "bidirectional"))
    )
    (net (code "254") (name "unconnected-(PCB1-11{slash}GPIO3-Pad11)") (class "Default")
      (node (ref "PCB1") (pin "11") (pinfunction "11/GPIO3_11") (pintype "bidirectional"))
    )
    (net (code "255") (name "unconnected-(PCB1-12{slash}NC-Pad12)") (class "Default")
      (node (ref "PCB1") (pin "12") (pinfunction "12/NC_12") (pintype "bidirectional"))
    )
    (net (code "256") (name "unconnected-(PCB1-13{slash}GND-Pad13)") (class "Default")
      (node (ref "PCB1") (pin "13") (pinfunction "13/GND_13") (pintype "bidirectional"))
    )
    (net (code "257") (name "unconnected-(PCB1-14{slash}NC-Pad14)") (class "Default")
      (node (ref "PCB1") (pin "14") (pinfunction "14/NC_14") (pintype "bidirectional"))
    )
    (net (code "258") (name "unconnected-(PCB1-15{slash}GPIO4-Pad15)") (class "Default")
      (node (ref "PCB1") (pin "15") (pinfunction "15/GPIO4_15") (pintype "bidirectional"))
    )
    (net (code "259") (name "unconnected-(PCB1-16{slash}NC-Pad16)") (class "Default")
      (node (ref "PCB1") (pin "16") (pinfunction "16/NC_16") (pintype "bidirectional"))
    )
    (net (code "260") (name "unconnected-(PCB1-17{slash}GPIO5-Pad17)") (class "Default")
      (node (ref "PCB1") (pin "17") (pinfunction "17/GPIO5_17") (pintype "bidirectional"))
    )
    (net (code "261") (name "unconnected-(PCB1-18{slash}NC-Pad18)") (class "Default")
      (node (ref "PCB1") (pin "18") (pinfunction "18/NC_18") (pintype "bidirectional"))
    )
    (net (code "262") (name "unconnected-(PCB1-19{slash}GND-Pad19)") (class "Default")
      (node (ref "PCB1") (pin "19") (pinfunction "19/GND_19") (pintype "bidirectional"))
    )
    (net (code "263") (name "unconnected-(PCB1-20{slash}NC-Pad20)") (class "Default")
      (node (ref "PCB1") (pin "20") (pinfunction "20/NC_20") (pintype "bidirectional"))
    )
    (net (code "264") (name "unconnected-(PCB1-21{slash}GPIO6-Pad21)") (class "Default")
      (node (ref "PCB1") (pin "21") (pinfunction "21/GPIO6_21") (pintype "bidirectional"))
    )
    (net (code "265") (name "unconnected-(PCB1-22{slash}NC-Pad22)") (class "Default")
      (node (ref "PCB1") (pin "22") (pinfunction "22/NC_22") (pintype "bidirectional"))
    )
    (net (code "266") (name "unconnected-(PCB1-24{slash}NC-Pad24)") (class "Default")
      (node (ref "PCB1") (pin "24") (pinfunction "24/NC_24") (pintype "bidirectional"))
    )
    (net (code "267") (name "unconnected-(PCB1-25{slash}GND-Pad25)") (class "Default")
      (node (ref "PCB1") (pin "25") (pinfunction "25/GND_25") (pintype "bidirectional"))
    )
    (net (code "268") (name "unconnected-(PCB1-26{slash}GND-Pad26)") (class "Default")
      (node (ref "PCB1") (pin "26") (pinfunction "26/GND_26") (pintype "bidirectional"))
    )
    (net (code "269") (name "unconnected-(PCB1-31{slash}GND-Pad31)") (class "Default")
      (node (ref "PCB1") (pin "31") (pinfunction "31/GND_31") (pintype "bidirectional"))
    )
    (net (code "270") (name "unconnected-(PCB1-32{slash}GND-Pad32)") (class "Default")
      (node (ref "PCB1") (pin "32") (pinfunction "32/GND_32") (pintype "bidirectional"))
    )
    (net (code "271") (name "unconnected-(PCB1-34{slash}GPIO30-Pad34)") (class "Default")
      (node (ref "PCB1") (pin "34") (pinfunction "34/GPIO30_34") (pintype "bidirectional"))
    )
    (net (code "272") (name "unconnected-(PCB1-37{slash}GND-Pad37)") (class "Default")
      (node (ref "PCB1") (pin "37") (pinfunction "37/GND_37") (pintype "bidirectional"))
    )
    (net (code "273") (name "unconnected-(PCB1-38{slash}GND-Pad38)") (class "Default")
      (node (ref "PCB1") (pin "38") (pinfunction "38/GND_38") (pintype "bidirectional"))
    )
    (net (code "274") (name "unconnected-(PCB1-39{slash}GPIO0-27_VREF-Pad39)") (class "Default")
      (node (ref "PCB1") (pin "39") (pinfunction "39/GPIO0-27_VREF_39") (pintype "bidirectional"))
    )
    (net (code "275") (name "unconnected-(PCB1-41{slash}GPIO28-45_VREF-Pad41)") (class "Default")
      (node (ref "PCB1") (pin "41") (pinfunction "41/GPIO28-45_VREF_41") (pintype "bidirectional"))
    )
    (net (code "276") (name "unconnected-(PCB1-43{slash}GND-Pad43)") (class "Default")
      (node (ref "PCB1") (pin "43") (pinfunction "43/GND_43") (pintype "bidirectional"))
    )
    (net (code "277") (name "unconnected-(PCB1-44{slash}GND-Pad44)") (class "Default")
      (node (ref "PCB1") (pin "44") (pinfunction "44/GND_44") (pintype "bidirectional"))
    )
    (net (code "278") (name "unconnected-(PCB1-45{slash}GPIO12-Pad45)") (class "Default")
      (node (ref "PCB1") (pin "45") (pinfunction "45/GPIO12_45") (pintype "bidirectional"))
    )
    (net (code "279") (name "unconnected-(PCB1-47{slash}GPIO13-Pad47)") (class "Default")
      (node (ref "PCB1") (pin "47") (pinfunction "47/GPIO13_47") (pintype "bidirectional"))
    )
    (net (code "280") (name "unconnected-(PCB1-49{slash}GND-Pad49)") (class "Default")
      (node (ref "PCB1") (pin "49") (pinfunction "49/GND_49") (pintype "bidirectional"))
    )
    (net (code "281") (name "unconnected-(PCB1-50{slash}GND-Pad50)") (class "Default")
      (node (ref "PCB1") (pin "50") (pinfunction "50/GND_50") (pintype "bidirectional"))
    )
    (net (code "282") (name "unconnected-(PCB1-51{slash}GPIO14-Pad51)") (class "Default")
      (node (ref "PCB1") (pin "51") (pinfunction "51/GPIO14_51") (pintype "bidirectional"))
    )
    (net (code "283") (name "unconnected-(PCB1-53{slash}GPIO15-Pad53)") (class "Default")
      (node (ref "PCB1") (pin "53") (pinfunction "53/GPIO15_53") (pintype "bidirectional"))
    )
    (net (code "284") (name "unconnected-(PCB1-55{slash}GND-Pad55)") (class "Default")
      (node (ref "PCB1") (pin "55") (pinfunction "55/GND_55") (pintype "bidirectional"))
    )
    (net (code "285") (name "unconnected-(PCB1-56{slash}GND-Pad56)") (class "Default")
      (node (ref "PCB1") (pin "56") (pinfunction "56/GND_56") (pintype "bidirectional"))
    )
    (net (code "286") (name "unconnected-(PCB1-57{slash}GPIO16-Pad57)") (class "Default")
      (node (ref "PCB1") (pin "57") (pinfunction "57/GPIO16_57") (pintype "bidirectional"))
    )
    (net (code "287") (name "unconnected-(PCB1-59{slash}GPIO17-Pad59)") (class "Default")
      (node (ref "PCB1") (pin "59") (pinfunction "59/GPIO17_59") (pintype "bidirectional"))
    )
    (net (code "288") (name "unconnected-(PCB1-61{slash}GND-Pad61)") (class "Default")
      (node (ref "PCB1") (pin "61") (pinfunction "61/GND_61") (pintype "bidirectional"))
    )
    (net (code "289") (name "unconnected-(PCB1-62{slash}GND-Pad62)") (class "Default")
      (node (ref "PCB1") (pin "62") (pinfunction "62/GND_62") (pintype "bidirectional"))
    )
    (net (code "290") (name "unconnected-(PCB1-63{slash}GPIO18-Pad63)") (class "Default")
      (node (ref "PCB1") (pin "63") (pinfunction "63/GPIO18_63") (pintype "bidirectional"))
    )
    (net (code "291") (name "unconnected-(PCB1-65{slash}GPIO19-Pad65)") (class "Default")
      (node (ref "PCB1") (pin "65") (pinfunction "65/GPIO19_65") (pintype "bidirectional"))
    )
    (net (code "292") (name "unconnected-(PCB1-67{slash}GND-Pad67)") (class "Default")
      (node (ref "PCB1") (pin "67") (pinfunction "67/GND_67") (pintype "bidirectional"))
    )
    (net (code "293") (name "unconnected-(PCB1-68{slash}GND-Pad68)") (class "Default")
      (node (ref "PCB1") (pin "68") (pinfunction "68/GND_68") (pintype "bidirectional"))
    )
    (net (code "294") (name "unconnected-(PCB1-73{slash}GND-Pad73)") (class "Default")
      (node (ref "PCB1") (pin "73") (pinfunction "73/GND_73") (pintype "bidirectional"))
    )
    (net (code "295") (name "unconnected-(PCB1-74{slash}GND-Pad74)") (class "Default")
      (node (ref "PCB1") (pin "74") (pinfunction "74/GND_74") (pintype "bidirectional"))
    )
    (net (code "296") (name "unconnected-(PCB1-79{slash}GND-Pad79)") (class "Default")
      (node (ref "PCB1") (pin "79") (pinfunction "79/GND_79") (pintype "bidirectional"))
    )
    (net (code "297") (name "unconnected-(PCB1-80{slash}GND-Pad80)") (class "Default")
      (node (ref "PCB1") (pin "80") (pinfunction "80/GND_80") (pintype "bidirectional"))
    )
    (net (code "298") (name "unconnected-(PCB1-85{slash}GND-Pad85)") (class "Default")
      (node (ref "PCB1") (pin "85") (pinfunction "85/GND_85") (pintype "bidirectional"))
    )
    (net (code "299") (name "unconnected-(PCB1-86{slash}GND-Pad86)") (class "Default")
      (node (ref "PCB1") (pin "86") (pinfunction "86/GND_86") (pintype "bidirectional"))
    )
    (net (code "300") (name "unconnected-(PCB1-90{slash}GPIO47_1V8-Pad90)") (class "Default")
      (node (ref "PCB1") (pin "90") (pinfunction "90/GPIO47_1V8_90") (pintype "bidirectional"))
    )
    (net (code "301") (name "unconnected-(PCB1-91{slash}GND-Pad91)") (class "Default")
      (node (ref "PCB1") (pin "91") (pinfunction "91/GND_91") (pintype "bidirectional"))
    )
    (net (code "302") (name "unconnected-(PCB1-92{slash}GND-Pad92)") (class "Default")
      (node (ref "PCB1") (pin "92") (pinfunction "92/GND_92") (pintype "bidirectional"))
    )
    (net (code "303") (name "unconnected-(PCB1-93{slash}DSI0_DN1*-Pad93)") (class "Default")
      (node (ref "PCB1") (pin "93") (pinfunction "93/DSI0_DN1*_93") (pintype "bidirectional"))
    )
    (net (code "304") (name "unconnected-(PCB1-94{slash}DSI1_DP0*-Pad94)") (class "Default")
      (node (ref "PCB1") (pin "94") (pinfunction "94/DSI1_DP0*_94") (pintype "bidirectional"))
    )
    (net (code "305") (name "unconnected-(PCB1-95{slash}DSI0_DP1*-Pad95)") (class "Default")
      (node (ref "PCB1") (pin "95") (pinfunction "95/DSI0_DP1*_95") (pintype "bidirectional"))
    )
    (net (code "306") (name "unconnected-(PCB1-96{slash}DSI1_DN0*-Pad96)") (class "Default")
      (node (ref "PCB1") (pin "96") (pinfunction "96/DSI1_DN0*_96") (pintype "bidirectional"))
    )
    (net (code "307") (name "unconnected-(PCB1-97{slash}GND-Pad97)") (class "Default")
      (node (ref "PCB1") (pin "97") (pinfunction "97/GND_97") (pintype "bidirectional"))
    )
    (net (code "308") (name "unconnected-(PCB1-98{slash}GND-Pad98)") (class "Default")
      (node (ref "PCB1") (pin "98") (pinfunction "98/GND_98") (pintype "bidirectional"))
    )
    (net (code "309") (name "unconnected-(PCB1-99{slash}DSI0_DN0*-Pad99)") (class "Default")
      (node (ref "PCB1") (pin "99") (pinfunction "99/DSI0_DN0*_99") (pintype "bidirectional"))
    )
    (net (code "310") (name "unconnected-(PCB1-100{slash}DSI1CP*-Pad100)") (class "Default")
      (node (ref "PCB1") (pin "100") (pinfunction "100/DSI1CP*_100") (pintype "bidirectional"))
    )
    (net (code "311") (name "unconnected-(PCB1-101{slash}DSI0_DP0*-Pad101)") (class "Default")
      (node (ref "PCB1") (pin "101") (pinfunction "101/DSI0_DP0*_101") (pintype "bidirectional"))
    )
    (net (code "312") (name "unconnected-(PCB1-102{slash}DSI1CN*-Pad102)") (class "Default")
      (node (ref "PCB1") (pin "102") (pinfunction "102/DSI1CN*_102") (pintype "bidirectional"))
    )
    (net (code "313") (name "unconnected-(PCB1-103{slash}GND-Pad103)") (class "Default")
      (node (ref "PCB1") (pin "103") (pinfunction "103/GND_103") (pintype "bidirectional"))
    )
    (net (code "314") (name "unconnected-(PCB1-104{slash}GND-Pad104)") (class "Default")
      (node (ref "PCB1") (pin "104") (pinfunction "104/GND_104") (pintype "bidirectional"))
    )
    (net (code "315") (name "unconnected-(PCB1-105{slash}DSI0_CN*-Pad105)") (class "Default")
      (node (ref "PCB1") (pin "105") (pinfunction "105/DSI0_CN*_105") (pintype "bidirectional"))
    )
    (net (code "316") (name "unconnected-(PCB1-106{slash}DSI1_DP3*-Pad106)") (class "Default")
      (node (ref "PCB1") (pin "106") (pinfunction "106/DSI1_DP3*_106") (pintype "bidirectional"))
    )
    (net (code "317") (name "unconnected-(PCB1-107{slash}DSI0_CP*-Pad107)") (class "Default")
      (node (ref "PCB1") (pin "107") (pinfunction "107/DSI0_CP*_107") (pintype "bidirectional"))
    )
    (net (code "318") (name "unconnected-(PCB1-108{slash}DSI1_DN3*-Pad108)") (class "Default")
      (node (ref "PCB1") (pin "108") (pinfunction "108/DSI1_DN3*_108") (pintype "bidirectional"))
    )
    (net (code "319") (name "unconnected-(PCB1-109{slash}GND-Pad109)") (class "Default")
      (node (ref "PCB1") (pin "109") (pinfunction "109/GND_109") (pintype "bidirectional"))
    )
    (net (code "320") (name "unconnected-(PCB1-110{slash}GND-Pad110)") (class "Default")
      (node (ref "PCB1") (pin "110") (pinfunction "110/GND_110") (pintype "bidirectional"))
    )
    (net (code "321") (name "unconnected-(PCB1-111{slash}HDMI_CK_N*-Pad111)") (class "Default")
      (node (ref "PCB1") (pin "111") (pinfunction "111/HDMI_CK_N*_111") (pintype "bidirectional"))
    )
    (net (code "322") (name "unconnected-(PCB1-112{slash}DSI1_DP2*-Pad112)") (class "Default")
      (node (ref "PCB1") (pin "112") (pinfunction "112/DSI1_DP2*_112") (pintype "bidirectional"))
    )
    (net (code "323") (name "unconnected-(PCB1-113{slash}HDMI_CK_P*-Pad113)") (class "Default")
      (node (ref "PCB1") (pin "113") (pinfunction "113/HDMI_CK_P*_113") (pintype "bidirectional"))
    )
    (net (code "324") (name "unconnected-(PCB1-114{slash}DSI1_DN2*-Pad114)") (class "Default")
      (node (ref "PCB1") (pin "114") (pinfunction "114/DSI1_DN2*_114") (pintype "bidirectional"))
    )
    (net (code "325") (name "unconnected-(PCB1-115{slash}GND-Pad115)") (class "Default")
      (node (ref "PCB1") (pin "115") (pinfunction "115/GND_115") (pintype "bidirectional"))
    )
    (net (code "326") (name "unconnected-(PCB1-116{slash}GND-Pad116)") (class "Default")
      (node (ref "PCB1") (pin "116") (pinfunction "116/GND_116") (pintype "bidirectional"))
    )
    (net (code "327") (name "unconnected-(PCB1-117{slash}HDMI_D0_N*-Pad117)") (class "Default")
      (node (ref "PCB1") (pin "117") (pinfunction "117/HDMI_D0_N*_117") (pintype "bidirectional"))
    )
    (net (code "328") (name "unconnected-(PCB1-118{slash}DSI1_DP1*-Pad118)") (class "Default")
      (node (ref "PCB1") (pin "118") (pinfunction "118/DSI1_DP1*_118") (pintype "bidirectional"))
    )
    (net (code "329") (name "unconnected-(PCB1-119{slash}HDMI_D0_P*-Pad119)") (class "Default")
      (node (ref "PCB1") (pin "119") (pinfunction "119/HDMI_D0_P*_119") (pintype "bidirectional"))
    )
    (net (code "330") (name "unconnected-(PCB1-120{slash}DSI1_DN1*-Pad120)") (class "Default")
      (node (ref "PCB1") (pin "120") (pinfunction "120/DSI1_DN1*_120") (pintype "bidirectional"))
    )
    (net (code "331") (name "unconnected-(PCB1-121{slash}GND-Pad121)") (class "Default")
      (node (ref "PCB1") (pin "121") (pinfunction "121/GND_121") (pintype "bidirectional"))
    )
    (net (code "332") (name "unconnected-(PCB1-122{slash}GND-Pad122)") (class "Default")
      (node (ref "PCB1") (pin "122") (pinfunction "122/GND_122") (pintype "bidirectional"))
    )
    (net (code "333") (name "unconnected-(PCB1-123{slash}HDMI_D1_N*-Pad123)") (class "Default")
      (node (ref "PCB1") (pin "123") (pinfunction "123/HDMI_D1_N*_123") (pintype "bidirectional"))
    )
    (net (code "334") (name "unconnected-(PCB1-124{slash}NC-Pad124)") (class "Default")
      (node (ref "PCB1") (pin "124") (pinfunction "124/NC_124") (pintype "bidirectional"))
    )
    (net (code "335") (name "unconnected-(PCB1-125{slash}HDMI_D1_P*-Pad125)") (class "Default")
      (node (ref "PCB1") (pin "125") (pinfunction "125/HDMI_D1_P*_125") (pintype "bidirectional"))
    )
    (net (code "336") (name "unconnected-(PCB1-126{slash}NC-Pad126)") (class "Default")
      (node (ref "PCB1") (pin "126") (pinfunction "126/NC_126") (pintype "bidirectional"))
    )
    (net (code "337") (name "unconnected-(PCB1-127{slash}GND-Pad127)") (class "Default")
      (node (ref "PCB1") (pin "127") (pinfunction "127/GND_127") (pintype "bidirectional"))
    )
    (net (code "338") (name "unconnected-(PCB1-128{slash}NC-Pad128)") (class "Default")
      (node (ref "PCB1") (pin "128") (pinfunction "128/NC_128") (pintype "bidirectional"))
    )
    (net (code "339") (name "unconnected-(PCB1-129{slash}HDMI_D2_N*-Pad129)") (class "Default")
      (node (ref "PCB1") (pin "129") (pinfunction "129/HDMI_D2_N*_129") (pintype "bidirectional"))
    )
    (net (code "340") (name "unconnected-(PCB1-130{slash}NC-Pad130)") (class "Default")
      (node (ref "PCB1") (pin "130") (pinfunction "130/NC_130") (pintype "bidirectional"))
    )
    (net (code "341") (name "unconnected-(PCB1-131{slash}HDMI_D2_P*-Pad131)") (class "Default")
      (node (ref "PCB1") (pin "131") (pinfunction "131/HDMI_D2_P*_131") (pintype "bidirectional"))
    )
    (net (code "342") (name "unconnected-(PCB1-132{slash}NC-Pad132)") (class "Default")
      (node (ref "PCB1") (pin "132") (pinfunction "132/NC_132") (pintype "bidirectional"))
    )
    (net (code "343") (name "unconnected-(PCB1-133{slash}GND-Pad133)") (class "Default")
      (node (ref "PCB1") (pin "133") (pinfunction "133/GND_133") (pintype "bidirectional"))
    )
    (net (code "344") (name "unconnected-(PCB1-135{slash}CAM1_DP3*-Pad135)") (class "Default")
      (node (ref "PCB1") (pin "135") (pinfunction "135/CAM1_DP3*_135") (pintype "bidirectional"))
    )
    (net (code "345") (name "unconnected-(PCB1-136{slash}CAM0_DP0*-Pad136)") (class "Default")
      (node (ref "PCB1") (pin "136") (pinfunction "136/CAM0_DP0*_136") (pintype "bidirectional"))
    )
    (net (code "346") (name "unconnected-(PCB1-137{slash}CAM1_DN3*-Pad137)") (class "Default")
      (node (ref "PCB1") (pin "137") (pinfunction "137/CAM1_DN3*_137") (pintype "bidirectional"))
    )
    (net (code "347") (name "unconnected-(PCB1-138{slash}CAM0_DN0*-Pad138)") (class "Default")
      (node (ref "PCB1") (pin "138") (pinfunction "138/CAM0_DN0*_138") (pintype "bidirectional"))
    )
    (net (code "348") (name "unconnected-(PCB1-139{slash}GND-Pad139)") (class "Default")
      (node (ref "PCB1") (pin "139") (pinfunction "139/GND_139") (pintype "bidirectional"))
    )
    (net (code "349") (name "unconnected-(PCB1-140{slash}GND-Pad140)") (class "Default")
      (node (ref "PCB1") (pin "140") (pinfunction "140/GND_140") (pintype "bidirectional"))
    )
    (net (code "350") (name "unconnected-(PCB1-141{slash}CAM1_DP2*-Pad141)") (class "Default")
      (node (ref "PCB1") (pin "141") (pinfunction "141/CAM1_DP2*_141") (pintype "bidirectional"))
    )
    (net (code "351") (name "unconnected-(PCB1-142{slash}CAM0_CP*-Pad142)") (class "Default")
      (node (ref "PCB1") (pin "142") (pinfunction "142/CAM0_CP*_142") (pintype "bidirectional"))
    )
    (net (code "352") (name "unconnected-(PCB1-143{slash}CAM1_DN2*-Pad143)") (class "Default")
      (node (ref "PCB1") (pin "143") (pinfunction "143/CAM1_DN2*_143") (pintype "bidirectional"))
    )
    (net (code "353") (name "unconnected-(PCB1-144{slash}CAM0_CN*-Pad144)") (class "Default")
      (node (ref "PCB1") (pin "144") (pinfunction "144/CAM0_CN*_144") (pintype "bidirectional"))
    )
    (net (code "354") (name "unconnected-(PCB1-145{slash}GND-Pad145)") (class "Default")
      (node (ref "PCB1") (pin "145") (pinfunction "145/GND_145") (pintype "bidirectional"))
    )
    (net (code "355") (name "unconnected-(PCB1-146{slash}GND-Pad146)") (class "Default")
      (node (ref "PCB1") (pin "146") (pinfunction "146/GND_146") (pintype "bidirectional"))
    )
    (net (code "356") (name "unconnected-(PCB1-147{slash}CAM1_CP*-Pad147)") (class "Default")
      (node (ref "PCB1") (pin "147") (pinfunction "147/CAM1_CP*_147") (pintype "bidirectional"))
    )
    (net (code "357") (name "unconnected-(PCB1-148{slash}CAM0_DP1*-Pad148)") (class "Default")
      (node (ref "PCB1") (pin "148") (pinfunction "148/CAM0_DP1*_148") (pintype "bidirectional"))
    )
    (net (code "358") (name "unconnected-(PCB1-149{slash}CAM1_CN*-Pad149)") (class "Default")
      (node (ref "PCB1") (pin "149") (pinfunction "149/CAM1_CN*_149") (pintype "bidirectional"))
    )
    (net (code "359") (name "unconnected-(PCB1-150{slash}CAM0_DN1*-Pad150)") (class "Default")
      (node (ref "PCB1") (pin "150") (pinfunction "150/CAM0_DN1*_150") (pintype "bidirectional"))
    )
    (net (code "360") (name "unconnected-(PCB1-151{slash}GND-Pad151)") (class "Default")
      (node (ref "PCB1") (pin "151") (pinfunction "151/GND_151") (pintype "bidirectional"))
    )
    (net (code "361") (name "unconnected-(PCB1-152{slash}GND-Pad152)") (class "Default")
      (node (ref "PCB1") (pin "152") (pinfunction "152/GND_152") (pintype "bidirectional"))
    )
    (net (code "362") (name "unconnected-(PCB1-153{slash}CAM1_DP1*-Pad153)") (class "Default")
      (node (ref "PCB1") (pin "153") (pinfunction "153/CAM1_DP1*_153") (pintype "bidirectional"))
    )
    (net (code "363") (name "unconnected-(PCB1-154{slash}NC-Pad154)") (class "Default")
      (node (ref "PCB1") (pin "154") (pinfunction "154/NC_154") (pintype "bidirectional"))
    )
    (net (code "364") (name "unconnected-(PCB1-155{slash}CAM1_DN1*-Pad155)") (class "Default")
      (node (ref "PCB1") (pin "155") (pinfunction "155/CAM1_DN1*_155") (pintype "bidirectional"))
    )
    (net (code "365") (name "unconnected-(PCB1-156{slash}NC-Pad156)") (class "Default")
      (node (ref "PCB1") (pin "156") (pinfunction "156/NC_156") (pintype "bidirectional"))
    )
    (net (code "366") (name "unconnected-(PCB1-157{slash}GND-Pad157)") (class "Default")
      (node (ref "PCB1") (pin "157") (pinfunction "157/GND_157") (pintype "bidirectional"))
    )
    (net (code "367") (name "unconnected-(PCB1-158{slash}NC-Pad158)") (class "Default")
      (node (ref "PCB1") (pin "158") (pinfunction "158/NC_158") (pintype "bidirectional"))
    )
    (net (code "368") (name "unconnected-(PCB1-159{slash}CAM1_DP0*-Pad159)") (class "Default")
      (node (ref "PCB1") (pin "159") (pinfunction "159/CAM1_DP0*_159") (pintype "bidirectional"))
    )
    (net (code "369") (name "unconnected-(PCB1-160{slash}NC-Pad160)") (class "Default")
      (node (ref "PCB1") (pin "160") (pinfunction "160/NC_160") (pintype "bidirectional"))
    )
    (net (code "370") (name "unconnected-(PCB1-161{slash}CAM1_DN0*-Pad161)") (class "Default")
      (node (ref "PCB1") (pin "161") (pinfunction "161/CAM1_DN0*_161") (pintype "bidirectional"))
    )
    (net (code "371") (name "unconnected-(PCB1-162{slash}NC-Pad162)") (class "Default")
      (node (ref "PCB1") (pin "162") (pinfunction "162/NC_162") (pintype "bidirectional"))
    )
    (net (code "372") (name "unconnected-(PCB1-163{slash}GND-Pad163)") (class "Default")
      (node (ref "PCB1") (pin "163") (pinfunction "163/GND_163") (pintype "bidirectional"))
    )
    (net (code "373") (name "unconnected-(PCB1-164{slash}GND-Pad164)") (class "Default")
      (node (ref "PCB1") (pin "164") (pinfunction "164/GND_164") (pintype "bidirectional"))
    )
    (net (code "374") (name "unconnected-(PCB1-166{slash}TVDAC-Pad166)") (class "Default")
      (node (ref "PCB1") (pin "166") (pinfunction "166/TVDAC_166") (pintype "bidirectional"))
    )
    (net (code "375") (name "unconnected-(PCB1-169{slash}GND-Pad169)") (class "Default")
      (node (ref "PCB1") (pin "169") (pinfunction "169/GND_169") (pintype "bidirectional"))
    )
    (net (code "376") (name "unconnected-(PCB1-170{slash}GND-Pad170)") (class "Default")
      (node (ref "PCB1") (pin "170") (pinfunction "170/GND_170") (pintype "bidirectional"))
    )
    (net (code "377") (name "unconnected-(PCB1-171{slash}HDMI_CEC-Pad171)") (class "Default")
      (node (ref "PCB1") (pin "171") (pinfunction "171/HDMI_CEC_171") (pintype "bidirectional"))
    )
    (net (code "378") (name "unconnected-(PCB1-172{slash}VC_TRST_N-Pad172)") (class "Default")
      (node (ref "PCB1") (pin "172") (pinfunction "172/VC_TRST_N_172") (pintype "bidirectional"))
    )
    (net (code "379") (name "unconnected-(PCB1-173{slash}HDMI_SDA-Pad173)") (class "Default")
      (node (ref "PCB1") (pin "173") (pinfunction "173/HDMI_SDA_173") (pintype "bidirectional"))
    )
    (net (code "380") (name "unconnected-(PCB1-174{slash}VC_TDI-Pad174)") (class "Default")
      (node (ref "PCB1") (pin "174") (pinfunction "174/VC_TDI_174") (pintype "bidirectional"))
    )
    (net (code "381") (name "unconnected-(PCB1-175{slash}HDMI_SCL-Pad175)") (class "Default")
      (node (ref "PCB1") (pin "175") (pinfunction "175/HDMI_SCL_175") (pintype "bidirectional"))
    )
    (net (code "382") (name "unconnected-(PCB1-176{slash}VC_TMS-Pad176)") (class "Default")
      (node (ref "PCB1") (pin "176") (pinfunction "176/VC_TMS_176") (pintype "bidirectional"))
    )
    (net (code "383") (name "unconnected-(PCB1-177{slash}RUN-Pad177)") (class "Default")
      (node (ref "PCB1") (pin "177") (pinfunction "177/RUN_177") (pintype "bidirectional"))
    )
    (net (code "384") (name "unconnected-(PCB1-178{slash}VC_TDO-Pad178)") (class "Default")
      (node (ref "PCB1") (pin "178") (pinfunction "178/VC_TDO_178") (pintype "bidirectional"))
    )
    (net (code "385") (name "unconnected-(PCB1-179{slash}VDD_CORE-Pad179)") (class "Default")
      (node (ref "PCB1") (pin "179") (pinfunction "179/VDD_CORE_179") (pintype "bidirectional"))
    )
    (net (code "386") (name "unconnected-(PCB1-180{slash}VC_TCK-Pad180)") (class "Default")
      (node (ref "PCB1") (pin "180") (pinfunction "180/VC_TCK_180") (pintype "bidirectional"))
    )
    (net (code "387") (name "unconnected-(PCB1-181{slash}GND-Pad181)") (class "Default")
      (node (ref "PCB1") (pin "181") (pinfunction "181/GND_181") (pintype "bidirectional"))
    )
    (net (code "388") (name "unconnected-(PCB1-182{slash}GND-Pad182)") (class "Default")
      (node (ref "PCB1") (pin "182") (pinfunction "182/GND_182") (pintype "bidirectional"))
    )
    (net (code "389") (name "unconnected-(PCB1-187{slash}GND-Pad187)") (class "Default")
      (node (ref "PCB1") (pin "187") (pinfunction "187/GND_187") (pintype "bidirectional"))
    )
    (net (code "390") (name "unconnected-(PCB1-188{slash}GND-Pad188)") (class "Default")
      (node (ref "PCB1") (pin "188") (pinfunction "188/GND_188") (pintype "bidirectional"))
    )
    (net (code "391") (name "unconnected-(PCB1-195{slash}GND-Pad195)") (class "Default")
      (node (ref "PCB1") (pin "195") (pinfunction "195/GND_195") (pintype "bidirectional"))
    )
    (net (code "392") (name "unconnected-(PCB1-196{slash}GND-Pad196)") (class "Default")
      (node (ref "PCB1") (pin "196") (pinfunction "196/GND_196") (pintype "bidirectional"))
    )
    (net (code "393") (name "unconnected-(TFT1-#RD-Pad35)") (class "Default")
      (node (ref "TFT1") (pin "35") (pinfunction "#RD_35") (pintype "bidirectional"))
    )
    (net (code "394") (name "unconnected-(TFT1-DE-Pad14)") (class "Default")
      (node (ref "TFT1") (pin "14") (pinfunction "DE_14") (pintype "bidirectional"))
    )
    (net (code "395") (name "unconnected-(TFT1-DOTCLK-Pad13)") (class "Default")
      (node (ref "TFT1") (pin "13") (pinfunction "DOTCLK_13") (pintype "bidirectional"))
    )
    (net (code "396") (name "unconnected-(TFT1-HSYNC-Pad12)") (class "Default")
      (node (ref "TFT1") (pin "12") (pinfunction "HSYNC_12") (pintype "bidirectional"))
    )
    (net (code "397") (name "unconnected-(TFT1-TE-Pad39)") (class "Default")
      (node (ref "TFT1") (pin "39") (pinfunction "TE_39") (pintype "bidirectional"))
    )
    (net (code "398") (name "unconnected-(TFT1-VSYNC-Pad11)") (class "Default")
      (node (ref "TFT1") (pin "11") (pinfunction "VSYNC_11") (pintype "bidirectional"))
    )
    (net (code "399") (name "unconnected-(U$1-NC1-Pad5)") (class "Default")
      (node (ref "U$1") (pin "5") (pinfunction "NC1_5") (pintype "bidirectional"))
    )
    (net (code "400") (name "unconnected-(U$1-NC2-Pad11)") (class "Default")
      (node (ref "U$1") (pin "11") (pinfunction "NC2_11") (pintype "bidirectional"))
    )
    (net (code "401") (name "unconnected-(U$5-ADJ-Pad4)") (class "Default")
      (node (ref "U$5") (pin "4") (pinfunction "ADJ_4") (pintype "bidirectional"))
    )
    (net (code "402") (name "unconnected-(UTSC-IN0{slash}GPIO-0-Pad8)") (class "Default")
      (node (ref "UTSC") (pin "8") (pinfunction "IN0/GPIO-0_8") (pintype "bidirectional"))
    )
    (net (code "403") (name "unconnected-(UTSC-IN3{slash}GPIO-3-Pad12)") (class "Default")
      (node (ref "UTSC") (pin "12") (pinfunction "IN3/GPIO-3_12") (pintype "bidirectional"))
    )
  )
)
